# K84.net
KiCad netlist of a schematic drawn in EAGLE
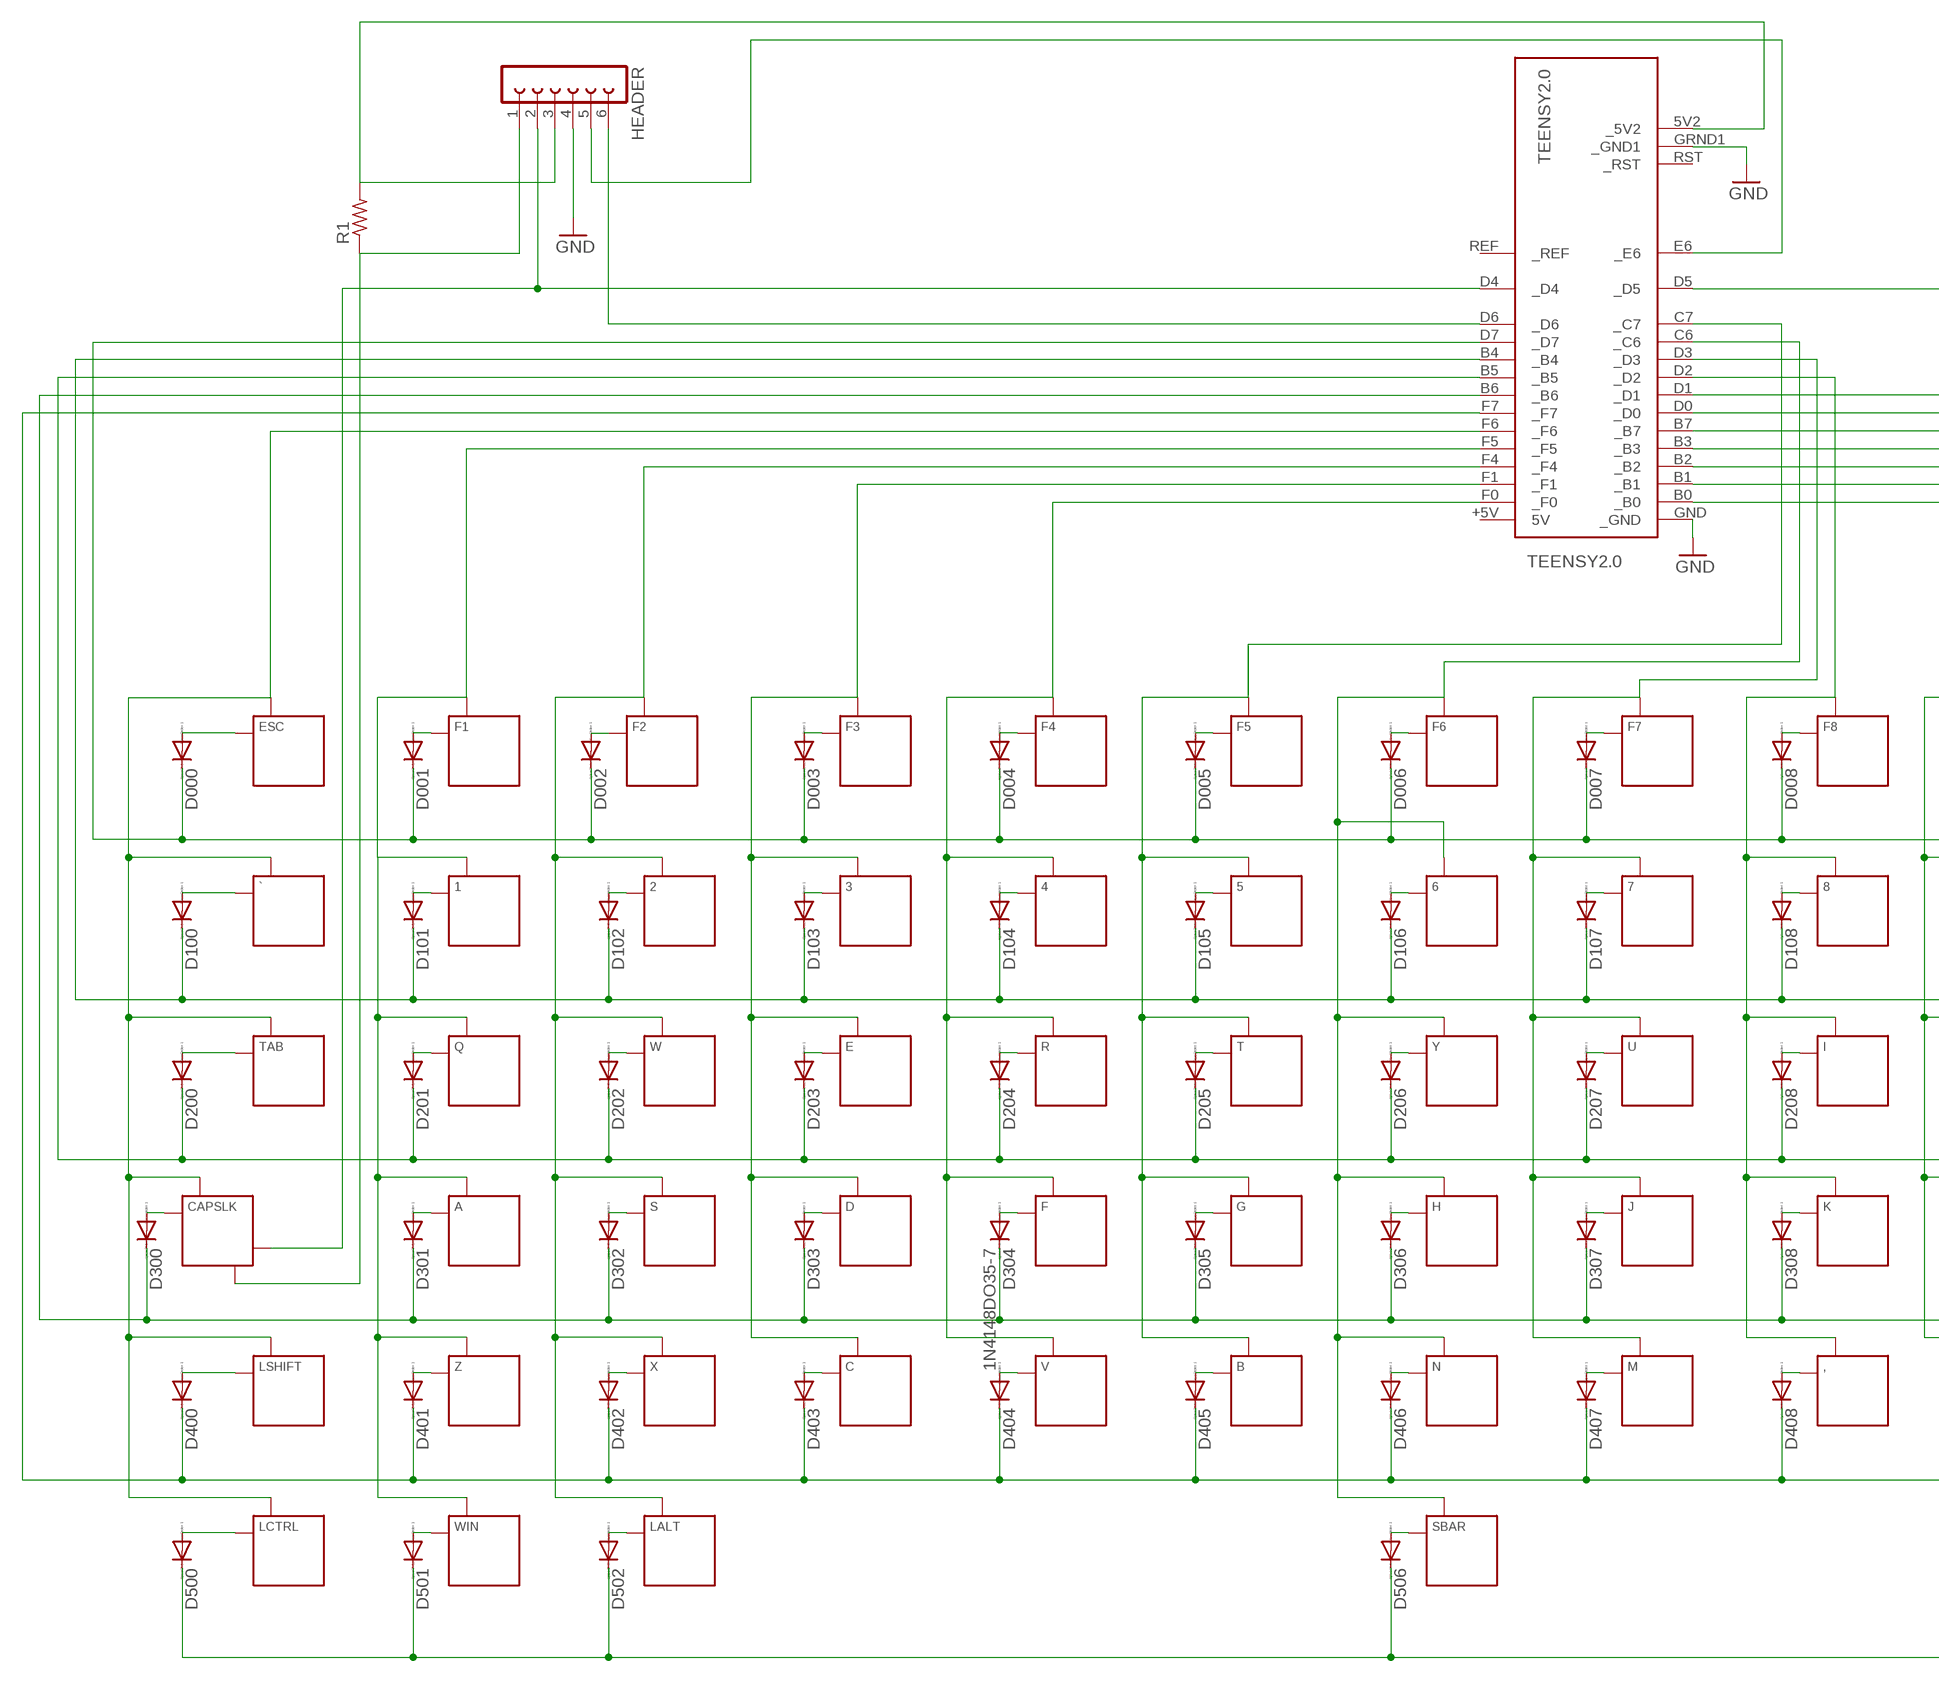
[diagram p0: schematic, sheet 1, part 1 of 2]
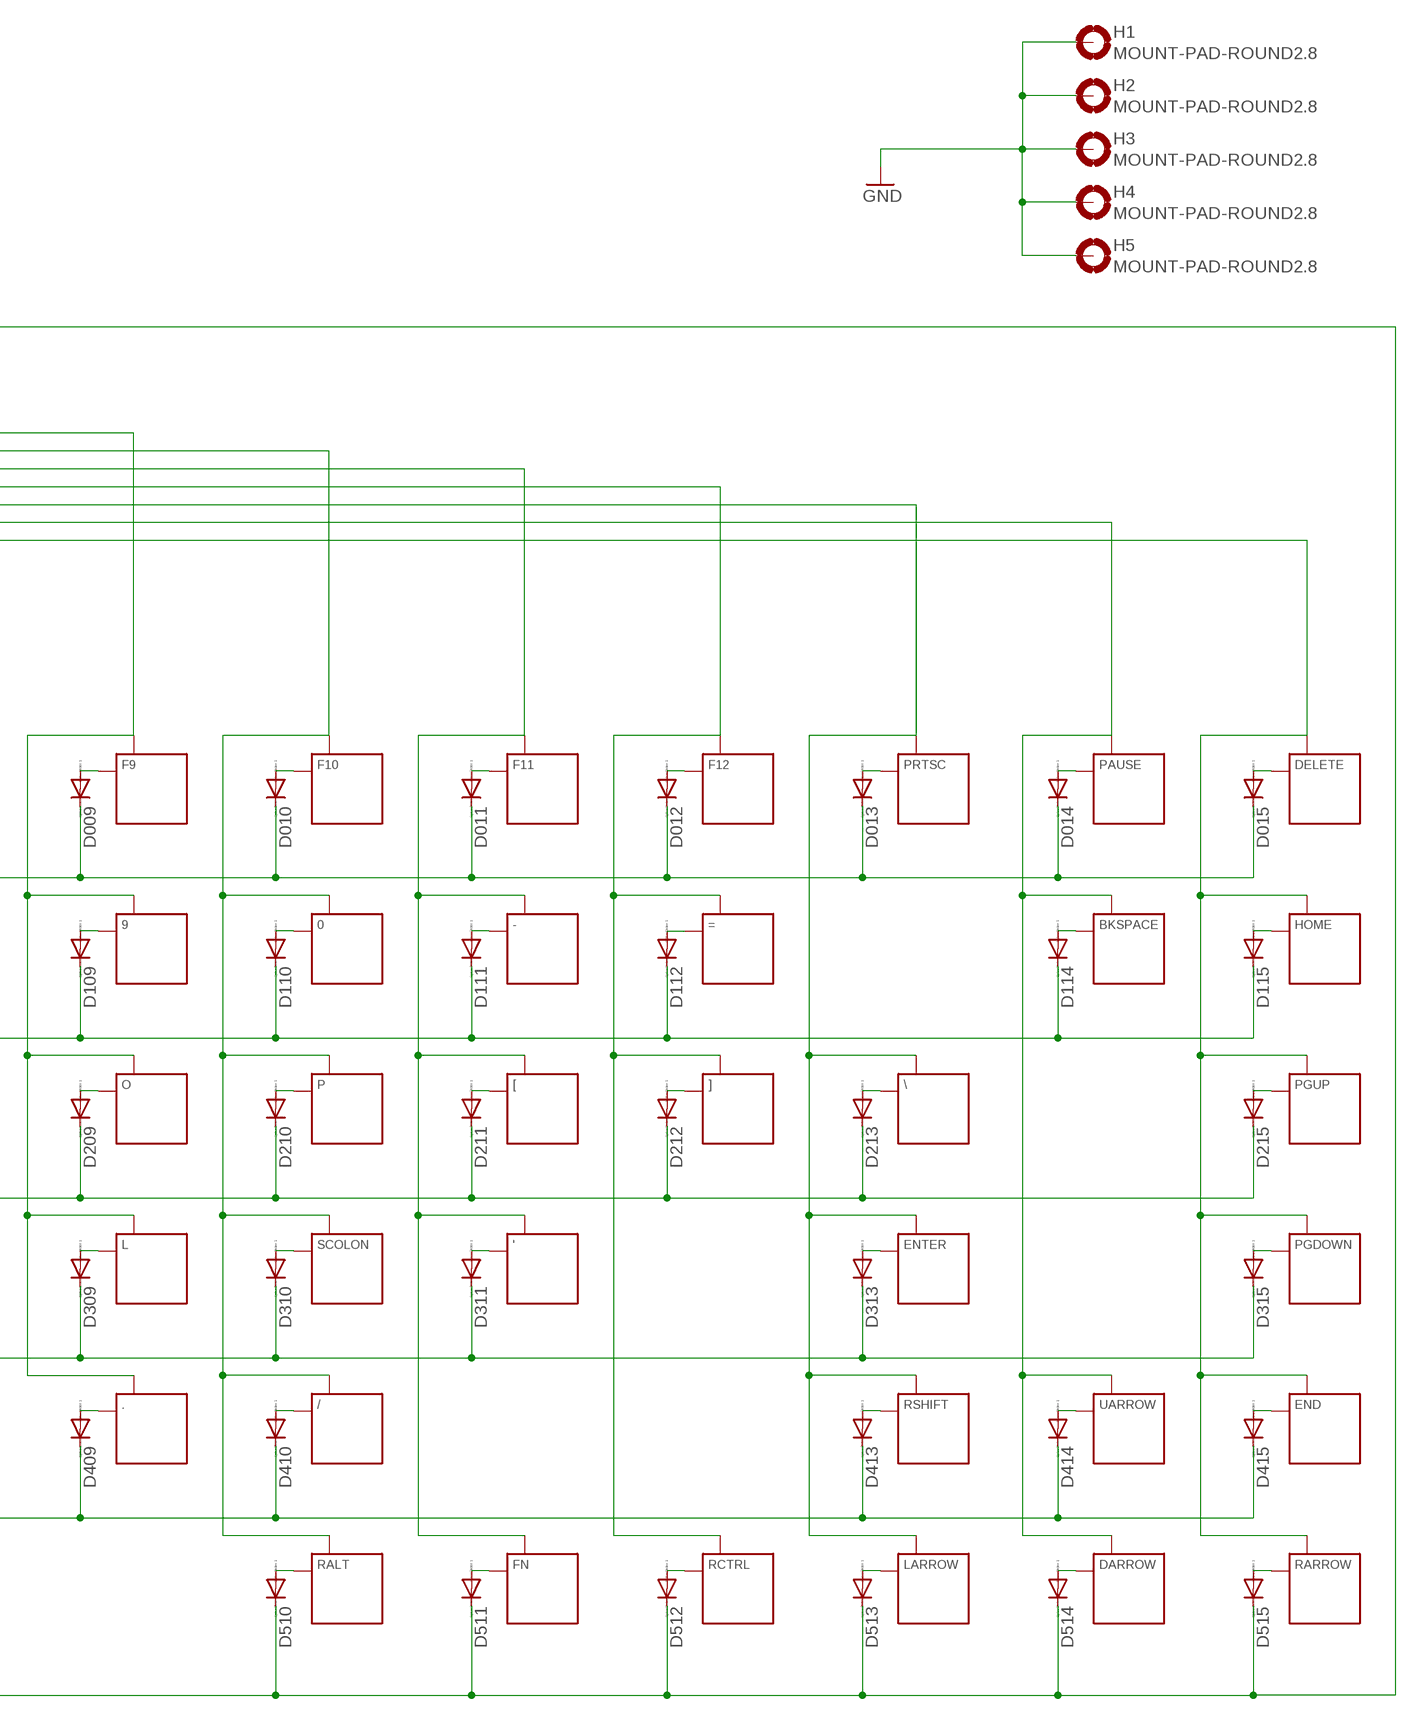
[diagram p1: schematic, sheet 1, part 2 of 2]

(export (version "E")
  (design (tool "Eeschema 10.0.6"))
  (components
    (comp (ref "'")
      (value "KEYSWITCH-PLAIN-MX-1U")
      (footprint "eagle-import:MX-1U")
      (libsource (lib "eagle-import") (part "KEYSWITCH-PLAIN-MX-1U"))
    )
    (comp (ref ",")
      (value "KEYSWITCH-PLAIN-MX-1U")
      (footprint "eagle-import:MX-1U")
      (libsource (lib "eagle-import") (part "KEYSWITCH-PLAIN-MX-1U"))
    )
    (comp (ref "-")
      (value "KEYSWITCH-PLAIN-MX-1U")
      (footprint "eagle-import:MX-1U")
      (libsource (lib "eagle-import") (part "KEYSWITCH-PLAIN-MX-1U"))
    )
    (comp (ref ".")
      (value "KEYSWITCH-PLAIN-MX-1U")
      (footprint "eagle-import:MX-1U")
      (libsource (lib "eagle-import") (part "KEYSWITCH-PLAIN-MX-1U"))
    )
    (comp (ref "/")
      (value "KEYSWITCH-PLAIN-MX-1U")
      (footprint "eagle-import:MX-1U")
      (libsource (lib "eagle-import") (part "KEYSWITCH-PLAIN-MX-1U"))
    )
    (comp (ref "0")
      (value "KEYSWITCH-PLAIN-MX-1U")
      (footprint "eagle-import:MX-1U")
      (libsource (lib "eagle-import") (part "KEYSWITCH-PLAIN-MX-1U"))
    )
    (comp (ref "1")
      (value "KEYSWITCH-PLAIN-MX-1U")
      (footprint "eagle-import:MX-1U")
      (libsource (lib "eagle-import") (part "KEYSWITCH-PLAIN-MX-1U"))
    )
    (comp (ref "2")
      (value "KEYSWITCH-PLAIN-MX-1U")
      (footprint "eagle-import:MX-1U")
      (libsource (lib "eagle-import") (part "KEYSWITCH-PLAIN-MX-1U"))
    )
    (comp (ref "3")
      (value "KEYSWITCH-PLAIN-MX-1U")
      (footprint "eagle-import:MX-1U")
      (libsource (lib "eagle-import") (part "KEYSWITCH-PLAIN-MX-1U"))
    )
    (comp (ref "4")
      (value "KEYSWITCH-PLAIN-MX-1U")
      (footprint "eagle-import:MX-1U")
      (libsource (lib "eagle-import") (part "KEYSWITCH-PLAIN-MX-1U"))
    )
    (comp (ref "5")
      (value "KEYSWITCH-PLAIN-MX-1U")
      (footprint "eagle-import:MX-1U")
      (libsource (lib "eagle-import") (part "KEYSWITCH-PLAIN-MX-1U"))
    )
    (comp (ref "6")
      (value "KEYSWITCH-PLAIN-MX-1U")
      (footprint "eagle-import:MX-1U")
      (libsource (lib "eagle-import") (part "KEYSWITCH-PLAIN-MX-1U"))
    )
    (comp (ref "7")
      (value "KEYSWITCH-PLAIN-MX-1U")
      (footprint "eagle-import:MX-1U")
      (libsource (lib "eagle-import") (part "KEYSWITCH-PLAIN-MX-1U"))
    )
    (comp (ref "8")
      (value "KEYSWITCH-PLAIN-MX-1U")
      (footprint "eagle-import:MX-1U")
      (libsource (lib "eagle-import") (part "KEYSWITCH-PLAIN-MX-1U"))
    )
    (comp (ref "9")
      (value "KEYSWITCH-PLAIN-MX-1U")
      (footprint "eagle-import:MX-1U")
      (libsource (lib "eagle-import") (part "KEYSWITCH-PLAIN-MX-1U"))
    )
    (comp (ref "=")
      (value "KEYSWITCH-PLAIN-MX-1U")
      (footprint "eagle-import:MX-1U")
      (libsource (lib "eagle-import") (part "KEYSWITCH-PLAIN-MX-1U"))
    )
    (comp (ref "A")
      (value "KEYSWITCH-PLAIN-MX-1U")
      (footprint "eagle-import:MX-1U")
      (libsource (lib "eagle-import") (part "KEYSWITCH-PLAIN-MX-1U"))
    )
    (comp (ref "B")
      (value "KEYSWITCH-PLAIN-MX-1U")
      (footprint "eagle-import:MX-1U")
      (libsource (lib "eagle-import") (part "KEYSWITCH-PLAIN-MX-1U"))
    )
    (comp (ref "BKSPACE")
      (value "KEYSWITCH-PLAIN-MX-2U")
      (footprint "eagle-import:MX-2U")
      (libsource (lib "eagle-import") (part "KEYSWITCH-PLAIN-MX-2U"))
    )
    (comp (ref "C")
      (value "KEYSWITCH-PLAIN-MX-1U")
      (footprint "eagle-import:MX-1U")
      (libsource (lib "eagle-import") (part "KEYSWITCH-PLAIN-MX-1U"))
    )
    (comp (ref "CAPSLK")
      (value "KEYSWITCH-LED-MX-1U-LED")
      (footprint "eagle-import:MX-1U-LED")
      (libsource (lib "eagle-import") (part "KEYSWITCH-LED-MX-1U-LED"))
    )
    (comp (ref "D")
      (value "KEYSWITCH-PLAIN-MX-1U")
      (footprint "eagle-import:MX-1U")
      (libsource (lib "eagle-import") (part "KEYSWITCH-PLAIN-MX-1U"))
    )
    (comp (ref "D000")
      (value "1N4148DO35-7")
      (footprint "eagle-import:DO35-7")
      (libsource (lib "eagle-import") (part "1N4148DO35-7"))
    )
    (comp (ref "D001")
      (value "1N4148DO35-7")
      (footprint "eagle-import:DO35-7")
      (libsource (lib "eagle-import") (part "1N4148DO35-7"))
    )
    (comp (ref "D002")
      (value "1N4148DO35-7")
      (footprint "eagle-import:DO35-7")
      (libsource (lib "eagle-import") (part "1N4148DO35-7"))
    )
    (comp (ref "D003")
      (value "1N4148DO35-7")
      (footprint "eagle-import:DO35-7")
      (libsource (lib "eagle-import") (part "1N4148DO35-7"))
    )
    (comp (ref "D004")
      (value "1N4148DO35-7")
      (footprint "eagle-import:DO35-7")
      (libsource (lib "eagle-import") (part "1N4148DO35-7"))
    )
    (comp (ref "D005")
      (value "1N4148DO35-7")
      (footprint "eagle-import:DO35-7")
      (libsource (lib "eagle-import") (part "1N4148DO35-7"))
    )
    (comp (ref "D006")
      (value "1N4148DO35-7")
      (footprint "eagle-import:DO35-7")
      (libsource (lib "eagle-import") (part "1N4148DO35-7"))
    )
    (comp (ref "D007")
      (value "1N4148DO35-7")
      (footprint "eagle-import:DO35-7")
      (libsource (lib "eagle-import") (part "1N4148DO35-7"))
    )
    (comp (ref "D008")
      (value "1N4148DO35-7")
      (footprint "eagle-import:DO35-7")
      (libsource (lib "eagle-import") (part "1N4148DO35-7"))
    )
    (comp (ref "D009")
      (value "1N4148DO35-7")
      (footprint "eagle-import:DO35-7")
      (libsource (lib "eagle-import") (part "1N4148DO35-7"))
    )
    (comp (ref "D010")
      (value "1N4148DO35-7")
      (footprint "eagle-import:DO35-7")
      (libsource (lib "eagle-import") (part "1N4148DO35-7"))
    )
    (comp (ref "D011")
      (value "1N4148DO35-7")
      (footprint "eagle-import:DO35-7")
      (libsource (lib "eagle-import") (part "1N4148DO35-7"))
    )
    (comp (ref "D012")
      (value "1N4148DO35-7")
      (footprint "eagle-import:DO35-7")
      (libsource (lib "eagle-import") (part "1N4148DO35-7"))
    )
    (comp (ref "D013")
      (value "1N4148DO35-7")
      (footprint "eagle-import:DO35-7")
      (libsource (lib "eagle-import") (part "1N4148DO35-7"))
    )
    (comp (ref "D014")
      (value "1N4148DO35-7")
      (footprint "eagle-import:DO35-7")
      (libsource (lib "eagle-import") (part "1N4148DO35-7"))
    )
    (comp (ref "D015")
      (value "1N4148DO35-7")
      (footprint "eagle-import:DO35-7")
      (libsource (lib "eagle-import") (part "1N4148DO35-7"))
    )
    (comp (ref "D100")
      (value "1N4148DO35-7")
      (footprint "eagle-import:DO35-7")
      (libsource (lib "eagle-import") (part "1N4148DO35-7"))
    )
    (comp (ref "D101")
      (value "1N4148DO35-7")
      (footprint "eagle-import:DO35-7")
      (libsource (lib "eagle-import") (part "1N4148DO35-7"))
    )
    (comp (ref "D102")
      (value "1N4148DO35-7")
      (footprint "eagle-import:DO35-7")
      (libsource (lib "eagle-import") (part "1N4148DO35-7"))
    )
    (comp (ref "D103")
      (value "1N4148DO35-7")
      (footprint "eagle-import:DO35-7")
      (libsource (lib "eagle-import") (part "1N4148DO35-7"))
    )
    (comp (ref "D104")
      (value "1N4148DO35-7")
      (footprint "eagle-import:DO35-7")
      (libsource (lib "eagle-import") (part "1N4148DO35-7"))
    )
    (comp (ref "D105")
      (value "1N4148DO35-7")
      (footprint "eagle-import:DO35-7")
      (libsource (lib "eagle-import") (part "1N4148DO35-7"))
    )
    (comp (ref "D106")
      (value "1N4148DO35-7")
      (footprint "eagle-import:DO35-7")
      (libsource (lib "eagle-import") (part "1N4148DO35-7"))
    )
    (comp (ref "D107")
      (value "1N4148DO35-7")
      (footprint "eagle-import:DO35-7")
      (libsource (lib "eagle-import") (part "1N4148DO35-7"))
    )
    (comp (ref "D108")
      (value "1N4148DO35-7")
      (footprint "eagle-import:DO35-7")
      (libsource (lib "eagle-import") (part "1N4148DO35-7"))
    )
    (comp (ref "D109")
      (value "1N4148DO35-7")
      (footprint "eagle-import:DO35-7")
      (libsource (lib "eagle-import") (part "1N4148DO35-7"))
    )
    (comp (ref "D110")
      (value "1N4148DO35-7")
      (footprint "eagle-import:DO35-7")
      (libsource (lib "eagle-import") (part "1N4148DO35-7"))
    )
    (comp (ref "D111")
      (value "1N4148DO35-7")
      (footprint "eagle-import:DO35-7")
      (libsource (lib "eagle-import") (part "1N4148DO35-7"))
    )
    (comp (ref "D112")
      (value "1N4148DO35-7")
      (footprint "eagle-import:DO35-7")
      (libsource (lib "eagle-import") (part "1N4148DO35-7"))
    )
    (comp (ref "D114")
      (value "1N4148DO35-7")
      (footprint "eagle-import:DO35-7")
      (libsource (lib "eagle-import") (part "1N4148DO35-7"))
    )
    (comp (ref "D115")
      (value "1N4148DO35-7")
      (footprint "eagle-import:DO35-7")
      (libsource (lib "eagle-import") (part "1N4148DO35-7"))
    )
    (comp (ref "D200")
      (value "1N4148DO35-7")
      (footprint "eagle-import:DO35-7")
      (libsource (lib "eagle-import") (part "1N4148DO35-7"))
    )
    (comp (ref "D201")
      (value "1N4148DO35-7")
      (footprint "eagle-import:DO35-7")
      (libsource (lib "eagle-import") (part "1N4148DO35-7"))
    )
    (comp (ref "D202")
      (value "1N4148DO35-7")
      (footprint "eagle-import:DO35-7")
      (libsource (lib "eagle-import") (part "1N4148DO35-7"))
    )
    (comp (ref "D203")
      (value "1N4148DO35-7")
      (footprint "eagle-import:DO35-7")
      (libsource (lib "eagle-import") (part "1N4148DO35-7"))
    )
    (comp (ref "D204")
      (value "1N4148DO35-7")
      (footprint "eagle-import:DO35-7")
      (libsource (lib "eagle-import") (part "1N4148DO35-7"))
    )
    (comp (ref "D205")
      (value "1N4148DO35-7")
      (footprint "eagle-import:DO35-7")
      (libsource (lib "eagle-import") (part "1N4148DO35-7"))
    )
    (comp (ref "D206")
      (value "1N4148DO35-7")
      (footprint "eagle-import:DO35-7")
      (libsource (lib "eagle-import") (part "1N4148DO35-7"))
    )
    (comp (ref "D207")
      (value "1N4148DO35-7")
      (footprint "eagle-import:DO35-7")
      (libsource (lib "eagle-import") (part "1N4148DO35-7"))
    )
    (comp (ref "D208")
      (value "1N4148DO35-7")
      (footprint "eagle-import:DO35-7")
      (libsource (lib "eagle-import") (part "1N4148DO35-7"))
    )
    (comp (ref "D209")
      (value "1N4148DO35-7")
      (footprint "eagle-import:DO35-7")
      (libsource (lib "eagle-import") (part "1N4148DO35-7"))
    )
    (comp (ref "D210")
      (value "1N4148DO35-7")
      (footprint "eagle-import:DO35-7")
      (libsource (lib "eagle-import") (part "1N4148DO35-7"))
    )
    (comp (ref "D211")
      (value "1N4148DO35-7")
      (footprint "eagle-import:DO35-7")
      (libsource (lib "eagle-import") (part "1N4148DO35-7"))
    )
    (comp (ref "D212")
      (value "1N4148DO35-7")
      (footprint "eagle-import:DO35-7")
      (libsource (lib "eagle-import") (part "1N4148DO35-7"))
    )
    (comp (ref "D213")
      (value "1N4148DO35-7")
      (footprint "eagle-import:DO35-7")
      (libsource (lib "eagle-import") (part "1N4148DO35-7"))
    )
    (comp (ref "D215")
      (value "1N4148DO35-7")
      (footprint "eagle-import:DO35-7")
      (libsource (lib "eagle-import") (part "1N4148DO35-7"))
    )
    (comp (ref "D300")
      (value "1N4148DO35-7")
      (footprint "eagle-import:DO35-7")
      (libsource (lib "eagle-import") (part "1N4148DO35-7"))
    )
    (comp (ref "D301")
      (value "1N4148DO35-7")
      (footprint "eagle-import:DO35-7")
      (libsource (lib "eagle-import") (part "1N4148DO35-7"))
    )
    (comp (ref "D302")
      (value "1N4148DO35-7")
      (footprint "eagle-import:DO35-7")
      (libsource (lib "eagle-import") (part "1N4148DO35-7"))
    )
    (comp (ref "D303")
      (value "1N4148DO35-7")
      (footprint "eagle-import:DO35-7")
      (libsource (lib "eagle-import") (part "1N4148DO35-7"))
    )
    (comp (ref "D304")
      (value "1N4148DO35-7")
      (footprint "eagle-import:DO35-7")
      (libsource (lib "eagle-import") (part "1N4148DO35-7"))
    )
    (comp (ref "D305")
      (value "1N4148DO35-7")
      (footprint "eagle-import:DO35-7")
      (libsource (lib "eagle-import") (part "1N4148DO35-7"))
    )
    (comp (ref "D306")
      (value "1N4148DO35-7")
      (footprint "eagle-import:DO35-7")
      (libsource (lib "eagle-import") (part "1N4148DO35-7"))
    )
    (comp (ref "D307")
      (value "1N4148DO35-7")
      (footprint "eagle-import:DO35-7")
      (libsource (lib "eagle-import") (part "1N4148DO35-7"))
    )
    (comp (ref "D308")
      (value "1N4148DO35-7")
      (footprint "eagle-import:DO35-7")
      (libsource (lib "eagle-import") (part "1N4148DO35-7"))
    )
    (comp (ref "D309")
      (value "1N4148DO35-7")
      (footprint "eagle-import:DO35-7")
      (libsource (lib "eagle-import") (part "1N4148DO35-7"))
    )
    (comp (ref "D310")
      (value "1N4148DO35-7")
      (footprint "eagle-import:DO35-7")
      (libsource (lib "eagle-import") (part "1N4148DO35-7"))
    )
    (comp (ref "D311")
      (value "1N4148DO35-7")
      (footprint "eagle-import:DO35-7")
      (libsource (lib "eagle-import") (part "1N4148DO35-7"))
    )
    (comp (ref "D313")
      (value "1N4148DO35-7")
      (footprint "eagle-import:DO35-7")
      (libsource (lib "eagle-import") (part "1N4148DO35-7"))
    )
    (comp (ref "D315")
      (value "1N4148DO35-7")
      (footprint "eagle-import:DO35-7")
      (libsource (lib "eagle-import") (part "1N4148DO35-7"))
    )
    (comp (ref "D400")
      (value "1N4148DO35-7")
      (footprint "eagle-import:DO35-7")
      (libsource (lib "eagle-import") (part "1N4148DO35-7"))
    )
    (comp (ref "D401")
      (value "1N4148DO35-7")
      (footprint "eagle-import:DO35-7")
      (libsource (lib "eagle-import") (part "1N4148DO35-7"))
    )
    (comp (ref "D402")
      (value "1N4148DO35-7")
      (footprint "eagle-import:DO35-7")
      (libsource (lib "eagle-import") (part "1N4148DO35-7"))
    )
    (comp (ref "D403")
      (value "1N4148DO35-7")
      (footprint "eagle-import:DO35-7")
      (libsource (lib "eagle-import") (part "1N4148DO35-7"))
    )
    (comp (ref "D404")
      (value "1N4148DO35-7")
      (footprint "eagle-import:DO35-7")
      (libsource (lib "eagle-import") (part "1N4148DO35-7"))
    )
    (comp (ref "D405")
      (value "1N4148DO35-7")
      (footprint "eagle-import:DO35-7")
      (libsource (lib "eagle-import") (part "1N4148DO35-7"))
    )
    (comp (ref "D406")
      (value "1N4148DO35-7")
      (footprint "eagle-import:DO35-7")
      (libsource (lib "eagle-import") (part "1N4148DO35-7"))
    )
    (comp (ref "D407")
      (value "1N4148DO35-7")
      (footprint "eagle-import:DO35-7")
      (libsource (lib "eagle-import") (part "1N4148DO35-7"))
    )
    (comp (ref "D408")
      (value "1N4148DO35-7")
      (footprint "eagle-import:DO35-7")
      (libsource (lib "eagle-import") (part "1N4148DO35-7"))
    )
    (comp (ref "D409")
      (value "1N4148DO35-7")
      (footprint "eagle-import:DO35-7")
      (libsource (lib "eagle-import") (part "1N4148DO35-7"))
    )
    (comp (ref "D410")
      (value "1N4148DO35-7")
      (footprint "eagle-import:DO35-7")
      (libsource (lib "eagle-import") (part "1N4148DO35-7"))
    )
    (comp (ref "D413")
      (value "1N4148DO35-7")
      (footprint "eagle-import:DO35-7")
      (libsource (lib "eagle-import") (part "1N4148DO35-7"))
    )
    (comp (ref "D414")
      (value "1N4148DO35-7")
      (footprint "eagle-import:DO35-7")
      (libsource (lib "eagle-import") (part "1N4148DO35-7"))
    )
    (comp (ref "D415")
      (value "1N4148DO35-7")
      (footprint "eagle-import:DO35-7")
      (libsource (lib "eagle-import") (part "1N4148DO35-7"))
    )
    (comp (ref "D500")
      (value "1N4148DO35-7")
      (footprint "eagle-import:DO35-7")
      (libsource (lib "eagle-import") (part "1N4148DO35-7"))
    )
    (comp (ref "D501")
      (value "1N4148DO35-7")
      (footprint "eagle-import:DO35-7")
      (libsource (lib "eagle-import") (part "1N4148DO35-7"))
    )
    (comp (ref "D502")
      (value "1N4148DO35-7")
      (footprint "eagle-import:DO35-7")
      (libsource (lib "eagle-import") (part "1N4148DO35-7"))
    )
    (comp (ref "D506")
      (value "1N4148DO35-7")
      (footprint "eagle-import:DO35-7")
      (libsource (lib "eagle-import") (part "1N4148DO35-7"))
    )
    (comp (ref "D510")
      (value "1N4148DO35-7")
      (footprint "eagle-import:DO35-7")
      (libsource (lib "eagle-import") (part "1N4148DO35-7"))
    )
    (comp (ref "D511")
      (value "1N4148DO35-7")
      (footprint "eagle-import:DO35-7")
      (libsource (lib "eagle-import") (part "1N4148DO35-7"))
    )
    (comp (ref "D512")
      (value "1N4148DO35-7")
      (footprint "eagle-import:DO35-7")
      (libsource (lib "eagle-import") (part "1N4148DO35-7"))
    )
    (comp (ref "D513")
      (value "1N4148DO35-7")
      (footprint "eagle-import:DO35-7")
      (libsource (lib "eagle-import") (part "1N4148DO35-7"))
    )
    (comp (ref "D514")
      (value "1N4148DO35-7")
      (footprint "eagle-import:DO35-7")
      (libsource (lib "eagle-import") (part "1N4148DO35-7"))
    )
    (comp (ref "D515")
      (value "1N4148DO35-7")
      (footprint "eagle-import:DO35-7")
      (libsource (lib "eagle-import") (part "1N4148DO35-7"))
    )
    (comp (ref "DARROW")
      (value "KEYSWITCH-PLAIN-MX-1U")
      (footprint "eagle-import:MX-1U")
      (libsource (lib "eagle-import") (part "KEYSWITCH-PLAIN-MX-1U"))
    )
    (comp (ref "DELETE")
      (value "KEYSWITCH-PLAIN-MX-1U")
      (footprint "eagle-import:MX-1U")
      (libsource (lib "eagle-import") (part "KEYSWITCH-PLAIN-MX-1U"))
    )
    (comp (ref "E")
      (value "KEYSWITCH-PLAIN-MX-1U")
      (footprint "eagle-import:MX-1U")
      (libsource (lib "eagle-import") (part "KEYSWITCH-PLAIN-MX-1U"))
    )
    (comp (ref "END")
      (value "KEYSWITCH-PLAIN-MX-1U")
      (footprint "eagle-import:MX-1U")
      (libsource (lib "eagle-import") (part "KEYSWITCH-PLAIN-MX-1U"))
    )
    (comp (ref "ENTER")
      (value "KEYSWITCH-PLAIN-MX-2U")
      (footprint "eagle-import:MX-2U")
      (libsource (lib "eagle-import") (part "KEYSWITCH-PLAIN-MX-2U"))
    )
    (comp (ref "ESC")
      (value "S001")
      (footprint "eagle-import:MX-1U")
      (libsource (lib "eagle-import") (part "KEYSWITCH-PLAIN-MX-1U"))
    )
    (comp (ref "F")
      (value "KEYSWITCH-PLAIN-MX-1U")
      (footprint "eagle-import:MX-1U")
      (libsource (lib "eagle-import") (part "KEYSWITCH-PLAIN-MX-1U"))
    )
    (comp (ref "F1")
      (value "KEYSWITCH-PLAIN-MX-1U")
      (footprint "eagle-import:MX-1U")
      (libsource (lib "eagle-import") (part "KEYSWITCH-PLAIN-MX-1U"))
    )
    (comp (ref "F2")
      (value "KEYSWITCH-PLAIN-MX-1U")
      (footprint "eagle-import:MX-1U")
      (libsource (lib "eagle-import") (part "KEYSWITCH-PLAIN-MX-1U"))
    )
    (comp (ref "F3")
      (value "KEYSWITCH-PLAIN-MX-1U")
      (footprint "eagle-import:MX-1U")
      (libsource (lib "eagle-import") (part "KEYSWITCH-PLAIN-MX-1U"))
    )
    (comp (ref "F4")
      (value "KEYSWITCH-PLAIN-MX-1U")
      (footprint "eagle-import:MX-1U")
      (libsource (lib "eagle-import") (part "KEYSWITCH-PLAIN-MX-1U"))
    )
    (comp (ref "F5")
      (value "KEYSWITCH-PLAIN-MX-1U")
      (footprint "eagle-import:MX-1U")
      (libsource (lib "eagle-import") (part "KEYSWITCH-PLAIN-MX-1U"))
    )
    (comp (ref "F6")
      (value "KEYSWITCH-PLAIN-MX-1U")
      (footprint "eagle-import:MX-1U")
      (libsource (lib "eagle-import") (part "KEYSWITCH-PLAIN-MX-1U"))
    )
    (comp (ref "F7")
      (value "KEYSWITCH-PLAIN-MX-1U")
      (footprint "eagle-import:MX-1U")
      (libsource (lib "eagle-import") (part "KEYSWITCH-PLAIN-MX-1U"))
    )
    (comp (ref "F8")
      (value "KEYSWITCH-PLAIN-MX-1U")
      (footprint "eagle-import:MX-1U")
      (libsource (lib "eagle-import") (part "KEYSWITCH-PLAIN-MX-1U"))
    )
    (comp (ref "F9")
      (value "KEYSWITCH-PLAIN-MX-1U")
      (footprint "eagle-import:MX-1U")
      (libsource (lib "eagle-import") (part "KEYSWITCH-PLAIN-MX-1U"))
    )
    (comp (ref "F10")
      (value "KEYSWITCH-PLAIN-MX-1U")
      (footprint "eagle-import:MX-1U")
      (libsource (lib "eagle-import") (part "KEYSWITCH-PLAIN-MX-1U"))
    )
    (comp (ref "F11")
      (value "KEYSWITCH-PLAIN-MX-1U")
      (footprint "eagle-import:MX-1U")
      (libsource (lib "eagle-import") (part "KEYSWITCH-PLAIN-MX-1U"))
    )
    (comp (ref "F12")
      (value "KEYSWITCH-PLAIN-MX-1U")
      (footprint "eagle-import:MX-1U")
      (libsource (lib "eagle-import") (part "KEYSWITCH-PLAIN-MX-1U"))
    )
    (comp (ref "FN")
      (value "KEYSWITCH-PLAIN-MX-1U")
      (footprint "eagle-import:MX-1U")
      (libsource (lib "eagle-import") (part "KEYSWITCH-PLAIN-MX-1U"))
    )
    (comp (ref "G")
      (value "KEYSWITCH-PLAIN-MX-1U")
      (footprint "eagle-import:MX-1U")
      (libsource (lib "eagle-import") (part "KEYSWITCH-PLAIN-MX-1U"))
    )
    (comp (ref "H")
      (value "KEYSWITCH-PLAIN-MX-1U")
      (footprint "eagle-import:MX-1U")
      (libsource (lib "eagle-import") (part "KEYSWITCH-PLAIN-MX-1U"))
    )
    (comp (ref "H1")
      (value "MOUNT-PAD-ROUND2.8")
      (footprint "eagle-import:2,8-PAD")
      (libsource (lib "eagle-import") (part "MOUNT-PAD-ROUND2.8"))
    )
    (comp (ref "H2")
      (value "MOUNT-PAD-ROUND2.8")
      (footprint "eagle-import:2,8-PAD")
      (libsource (lib "eagle-import") (part "MOUNT-PAD-ROUND2.8"))
    )
    (comp (ref "H3")
      (value "MOUNT-PAD-ROUND2.8")
      (footprint "eagle-import:2,8-PAD")
      (libsource (lib "eagle-import") (part "MOUNT-PAD-ROUND2.8"))
    )
    (comp (ref "H4")
      (value "MOUNT-PAD-ROUND2.8")
      (footprint "eagle-import:2,8-PAD")
      (libsource (lib "eagle-import") (part "MOUNT-PAD-ROUND2.8"))
    )
    (comp (ref "H5")
      (value "MOUNT-PAD-ROUND2.8")
      (footprint "eagle-import:2,8-PAD")
      (libsource (lib "eagle-import") (part "MOUNT-PAD-ROUND2.8"))
    )
    (comp (ref "HEADER")
      (value "FE06-1")
      (footprint "eagle-import:FE06")
      (libsource (lib "eagle-import") (part "FE06-1"))
    )
    (comp (ref "HOME")
      (value "KEYSWITCH-PLAIN-MX-1U")
      (footprint "eagle-import:MX-1U")
      (libsource (lib "eagle-import") (part "KEYSWITCH-PLAIN-MX-1U"))
    )
    (comp (ref "I")
      (value "KEYSWITCH-PLAIN-MX-1U")
      (footprint "eagle-import:MX-1U")
      (libsource (lib "eagle-import") (part "KEYSWITCH-PLAIN-MX-1U"))
    )
    (comp (ref "J")
      (value "KEYSWITCH-PLAIN-MX-1U")
      (footprint "eagle-import:MX-1U")
      (libsource (lib "eagle-import") (part "KEYSWITCH-PLAIN-MX-1U"))
    )
    (comp (ref "K")
      (value "KEYSWITCH-PLAIN-MX-1U")
      (footprint "eagle-import:MX-1U")
      (libsource (lib "eagle-import") (part "KEYSWITCH-PLAIN-MX-1U"))
    )
    (comp (ref "L")
      (value "KEYSWITCH-PLAIN-MX-1U")
      (footprint "eagle-import:MX-1U")
      (libsource (lib "eagle-import") (part "KEYSWITCH-PLAIN-MX-1U"))
    )
    (comp (ref "LALT")
      (value "KEYSWITCH-PLAIN-MX-1U")
      (footprint "eagle-import:MX-1U")
      (libsource (lib "eagle-import") (part "KEYSWITCH-PLAIN-MX-1U"))
    )
    (comp (ref "LARROW")
      (value "KEYSWITCH-PLAIN-MX-1U")
      (footprint "eagle-import:MX-1U")
      (libsource (lib "eagle-import") (part "KEYSWITCH-PLAIN-MX-1U"))
    )
    (comp (ref "LCTRL")
      (value "KEYSWITCH-PLAIN-MX-1U")
      (footprint "eagle-import:MX-1U")
      (libsource (lib "eagle-import") (part "KEYSWITCH-PLAIN-MX-1U"))
    )
    (comp (ref "LSHIFT")
      (value "KEYSWITCH-PLAIN-MX-2U")
      (footprint "eagle-import:MX-2U")
      (libsource (lib "eagle-import") (part "KEYSWITCH-PLAIN-MX-2U"))
    )
    (comp (ref "M")
      (value "KEYSWITCH-PLAIN-MX-1U")
      (footprint "eagle-import:MX-1U")
      (libsource (lib "eagle-import") (part "KEYSWITCH-PLAIN-MX-1U"))
    )
    (comp (ref "N")
      (value "KEYSWITCH-PLAIN-MX-1U")
      (footprint "eagle-import:MX-1U")
      (libsource (lib "eagle-import") (part "KEYSWITCH-PLAIN-MX-1U"))
    )
    (comp (ref "O")
      (value "KEYSWITCH-PLAIN-MX-1U")
      (footprint "eagle-import:MX-1U")
      (libsource (lib "eagle-import") (part "KEYSWITCH-PLAIN-MX-1U"))
    )
    (comp (ref "P")
      (value "KEYSWITCH-PLAIN-MX-1U")
      (footprint "eagle-import:MX-1U")
      (libsource (lib "eagle-import") (part "KEYSWITCH-PLAIN-MX-1U"))
    )
    (comp (ref "PAUSE")
      (value "KEYSWITCH-PLAIN-MX-1U")
      (footprint "eagle-import:MX-1U")
      (libsource (lib "eagle-import") (part "KEYSWITCH-PLAIN-MX-1U"))
    )
    (comp (ref "PGDOWN")
      (value "KEYSWITCH-PLAIN-MX-1U")
      (footprint "eagle-import:MX-1U")
      (libsource (lib "eagle-import") (part "KEYSWITCH-PLAIN-MX-1U"))
    )
    (comp (ref "PGUP")
      (value "KEYSWITCH-PLAIN-MX-1U")
      (footprint "eagle-import:MX-1U")
      (libsource (lib "eagle-import") (part "KEYSWITCH-PLAIN-MX-1U"))
    )
    (comp (ref "PRTSC")
      (value "KEYSWITCH-PLAIN-MX-1U")
      (footprint "eagle-import:MX-1U")
      (libsource (lib "eagle-import") (part "KEYSWITCH-PLAIN-MX-1U"))
    )
    (comp (ref "Q")
      (value "KEYSWITCH-PLAIN-MX-1U")
      (footprint "eagle-import:MX-1U")
      (libsource (lib "eagle-import") (part "KEYSWITCH-PLAIN-MX-1U"))
    )
    (comp (ref "R")
      (value "KEYSWITCH-PLAIN-MX-1U")
      (footprint "eagle-import:MX-1U")
      (libsource (lib "eagle-import") (part "KEYSWITCH-PLAIN-MX-1U"))
    )
    (comp (ref "R1")
      (value "R-US_0204/7")
      (footprint "eagle-import:0204_7")
      (libsource (lib "eagle-import") (part "R-US_0204/7"))
    )
    (comp (ref "RALT")
      (value "KEYSWITCH-PLAIN-MX-1U")
      (footprint "eagle-import:MX-1U")
      (libsource (lib "eagle-import") (part "KEYSWITCH-PLAIN-MX-1U"))
    )
    (comp (ref "RARROW")
      (value "KEYSWITCH-PLAIN-MX-1U")
      (footprint "eagle-import:MX-1U")
      (libsource (lib "eagle-import") (part "KEYSWITCH-PLAIN-MX-1U"))
    )
    (comp (ref "RCTRL")
      (value "KEYSWITCH-PLAIN-MX-1U")
      (footprint "eagle-import:MX-1U")
      (libsource (lib "eagle-import") (part "KEYSWITCH-PLAIN-MX-1U"))
    )
    (comp (ref "RSHIFT")
      (value "KEYSWITCH-PLAIN-MX-1U")
      (footprint "eagle-import:MX-1U")
      (libsource (lib "eagle-import") (part "KEYSWITCH-PLAIN-MX-1U"))
    )
    (comp (ref "S")
      (value "KEYSWITCH-PLAIN-MX-1U")
      (footprint "eagle-import:MX-1U")
      (libsource (lib "eagle-import") (part "KEYSWITCH-PLAIN-MX-1U"))
    )
    (comp (ref "SBAR")
      (value "KEYSWITCH-PLAIN-MX-6.25U-FLIPPED")
      (footprint "eagle-import:MX-6.25U-FLIPPED")
      (libsource (lib "eagle-import") (part "KEYSWITCH-PLAIN-MX-6.25U-FLIPPED"))
    )
    (comp (ref "SCOLON")
      (value "KEYSWITCH-PLAIN-MX-1U")
      (footprint "eagle-import:MX-1U")
      (libsource (lib "eagle-import") (part "KEYSWITCH-PLAIN-MX-1U"))
    )
    (comp (ref "T")
      (value "KEYSWITCH-PLAIN-MX-1U")
      (footprint "eagle-import:MX-1U")
      (libsource (lib "eagle-import") (part "KEYSWITCH-PLAIN-MX-1U"))
    )
    (comp (ref "TAB")
      (value "KEYSWITCH-PLAIN-MX-1U")
      (footprint "eagle-import:MX-1U")
      (libsource (lib "eagle-import") (part "KEYSWITCH-PLAIN-MX-1U"))
    )
    (comp (ref "TEENSY2.0")
      (value "TEENSY2.0")
      (footprint "eagle-import:TEENSY2.0")
      (libsource (lib "eagle-import") (part "TEENSY2.0"))
    )
    (comp (ref "U")
      (value "KEYSWITCH-PLAIN-MX-1U")
      (footprint "eagle-import:MX-1U")
      (libsource (lib "eagle-import") (part "KEYSWITCH-PLAIN-MX-1U"))
    )
    (comp (ref "UARROW")
      (value "KEYSWITCH-PLAIN-MX-1U")
      (footprint "eagle-import:MX-1U")
      (libsource (lib "eagle-import") (part "KEYSWITCH-PLAIN-MX-1U"))
    )
    (comp (ref "V")
      (value "KEYSWITCH-PLAIN-MX-1U")
      (footprint "eagle-import:MX-1U")
      (libsource (lib "eagle-import") (part "KEYSWITCH-PLAIN-MX-1U"))
    )
    (comp (ref "W")
      (value "KEYSWITCH-PLAIN-MX-1U")
      (footprint "eagle-import:MX-1U")
      (libsource (lib "eagle-import") (part "KEYSWITCH-PLAIN-MX-1U"))
    )
    (comp (ref "WIN")
      (value "KEYSWITCH-PLAIN-MX-1U")
      (footprint "eagle-import:MX-1U")
      (libsource (lib "eagle-import") (part "KEYSWITCH-PLAIN-MX-1U"))
    )
    (comp (ref "X")
      (value "KEYSWITCH-PLAIN-MX-1U")
      (footprint "eagle-import:MX-1U")
      (libsource (lib "eagle-import") (part "KEYSWITCH-PLAIN-MX-1U"))
    )
    (comp (ref "Y")
      (value "KEYSWITCH-PLAIN-MX-1U")
      (footprint "eagle-import:MX-1U")
      (libsource (lib "eagle-import") (part "KEYSWITCH-PLAIN-MX-1U"))
    )
    (comp (ref "Z")
      (value "KEYSWITCH-PLAIN-MX-1U")
      (footprint "eagle-import:MX-1U")
      (libsource (lib "eagle-import") (part "KEYSWITCH-PLAIN-MX-1U"))
    )
    (comp (ref "[")
      (value "KEYSWITCH-PLAIN-MX-1U")
      (footprint "eagle-import:MX-1U")
      (libsource (lib "eagle-import") (part "KEYSWITCH-PLAIN-MX-1U"))
    )
    (comp (ref "\\\\")
      (value "KEYSWITCH-PLAIN-MX-1U")
      (footprint "eagle-import:MX-1U")
      (libsource (lib "eagle-import") (part "KEYSWITCH-PLAIN-MX-1U"))
    )
    (comp (ref "]")
      (value "KEYSWITCH-PLAIN-MX-1U")
      (footprint "eagle-import:MX-1U")
      (libsource (lib "eagle-import") (part "KEYSWITCH-PLAIN-MX-1U"))
    )
    (comp (ref "`")
      (value "KEYSWITCH-PLAIN-MX-1U")
      (footprint "eagle-import:MX-1U")
      (libsource (lib "eagle-import") (part "KEYSWITCH-PLAIN-MX-1U"))
    )
  )
  (nets
    (net (code "1") (name "GND") (class "Default")
      (node (ref "H1") (pin "B2,8") (pinfunction "MOUNT_B2,8") (pintype "passive"))
      (node (ref "H2") (pin "B2,8") (pinfunction "MOUNT_B2,8") (pintype "passive"))
      (node (ref "H3") (pin "B2,8") (pinfunction "MOUNT_B2,8") (pintype "passive"))
      (node (ref "H4") (pin "B2,8") (pinfunction "MOUNT_B2,8") (pintype "passive"))
      (node (ref "H5") (pin "B2,8") (pinfunction "MOUNT_B2,8") (pintype "passive"))
      (node (ref "HEADER") (pin "4") (pinfunction "4_4") (pintype "passive"))
      (node (ref "TEENSY2.0") (pin "GND") (pinfunction "_GND_GND") (pintype "bidirectional"))
      (node (ref "TEENSY2.0") (pin "GRND1") (pinfunction "_GND1_GRND1") (pintype "bidirectional"))
    )
    (net (code "2") (name "Net-('-P0)") (class "Default")
      (node (ref "'") (pin "MX1") (pinfunction "P0_MX1") (pintype "bidirectional"))
      (node (ref "D311") (pin "A") (pinfunction "A_A") (pintype "passive"))
    )
    (net (code "3") (name "Net-('-P1)") (class "Default")
      (node (ref "'") (pin "MX2") (pinfunction "P1_MX2") (pintype "bidirectional"))
      (node (ref "-") (pin "MX2") (pinfunction "P1_MX2") (pintype "bidirectional"))
      (node (ref "F11") (pin "MX2") (pinfunction "P1_MX2") (pintype "bidirectional"))
      (node (ref "FN") (pin "MX2") (pinfunction "P1_MX2") (pintype "bidirectional"))
      (node (ref "TEENSY2.0") (pin "B7") (pinfunction "_B7_B7") (pintype "bidirectional"))
      (node (ref "[") (pin "MX2") (pinfunction "P1_MX2") (pintype "bidirectional"))
    )
    (net (code "4") (name "Net-(,-P0)") (class "Default")
      (node (ref ",") (pin "MX1") (pinfunction "P0_MX1") (pintype "bidirectional"))
      (node (ref "D408") (pin "A") (pinfunction "A_A") (pintype "passive"))
    )
    (net (code "5") (name "Net-(,-P1)") (class "Default")
      (node (ref ",") (pin "MX2") (pinfunction "P1_MX2") (pintype "bidirectional"))
      (node (ref "8") (pin "MX2") (pinfunction "P1_MX2") (pintype "bidirectional"))
      (node (ref "F8") (pin "MX2") (pinfunction "P1_MX2") (pintype "bidirectional"))
      (node (ref "I") (pin "MX2") (pinfunction "P1_MX2") (pintype "bidirectional"))
      (node (ref "K") (pin "MX2") (pinfunction "P1_MX2") (pintype "bidirectional"))
      (node (ref "TEENSY2.0") (pin "D2") (pinfunction "_D2_D2") (pintype "bidirectional"))
    )
    (net (code "6") (name "Net-(--P0)") (class "Default")
      (node (ref "-") (pin "MX1") (pinfunction "P0_MX1") (pintype "bidirectional"))
      (node (ref "D111") (pin "A") (pinfunction "A_A") (pintype "passive"))
    )
    (net (code "7") (name "Net-(.-P0)") (class "Default")
      (node (ref ".") (pin "MX1") (pinfunction "P0_MX1") (pintype "bidirectional"))
      (node (ref "D409") (pin "A") (pinfunction "A_A") (pintype "passive"))
    )
    (net (code "8") (name "Net-(.-P1)") (class "Default")
      (node (ref ".") (pin "MX2") (pinfunction "P1_MX2") (pintype "bidirectional"))
      (node (ref "9") (pin "MX2") (pinfunction "P1_MX2") (pintype "bidirectional"))
      (node (ref "F9") (pin "MX2") (pinfunction "P1_MX2") (pintype "bidirectional"))
      (node (ref "L") (pin "MX2") (pinfunction "P1_MX2") (pintype "bidirectional"))
      (node (ref "O") (pin "MX2") (pinfunction "P1_MX2") (pintype "bidirectional"))
      (node (ref "TEENSY2.0") (pin "D1") (pinfunction "_D1_D1") (pintype "bidirectional"))
    )
    (net (code "9") (name "Net-(/-P0)") (class "Default")
      (node (ref "/") (pin "MX1") (pinfunction "P0_MX1") (pintype "bidirectional"))
      (node (ref "D410") (pin "A") (pinfunction "A_A") (pintype "passive"))
    )
    (net (code "10") (name "Net-(/-P1)") (class "Default")
      (node (ref "/") (pin "MX2") (pinfunction "P1_MX2") (pintype "bidirectional"))
      (node (ref "0") (pin "MX2") (pinfunction "P1_MX2") (pintype "bidirectional"))
      (node (ref "F10") (pin "MX2") (pinfunction "P1_MX2") (pintype "bidirectional"))
      (node (ref "P") (pin "MX2") (pinfunction "P1_MX2") (pintype "bidirectional"))
      (node (ref "RALT") (pin "MX2") (pinfunction "P1_MX2") (pintype "bidirectional"))
      (node (ref "SCOLON") (pin "MX2") (pinfunction "P1_MX2") (pintype "bidirectional"))
      (node (ref "TEENSY2.0") (pin "D0") (pinfunction "_D0_D0") (pintype "bidirectional"))
    )
    (net (code "11") (name "Net-(0-P0)") (class "Default")
      (node (ref "0") (pin "MX1") (pinfunction "P0_MX1") (pintype "bidirectional"))
      (node (ref "D110") (pin "A") (pinfunction "A_A") (pintype "passive"))
    )
    (net (code "12") (name "Net-(1-P0)") (class "Default")
      (node (ref "1") (pin "MX1") (pinfunction "P0_MX1") (pintype "bidirectional"))
      (node (ref "D101") (pin "A") (pinfunction "A_A") (pintype "passive"))
    )
    (net (code "13") (name "Net-(1-P1)") (class "Default")
      (node (ref "1") (pin "MX2") (pinfunction "P1_MX2") (pintype "bidirectional"))
      (node (ref "A") (pin "MX2") (pinfunction "P1_MX2") (pintype "bidirectional"))
      (node (ref "F1") (pin "MX2") (pinfunction "P1_MX2") (pintype "bidirectional"))
      (node (ref "Q") (pin "MX2") (pinfunction "P1_MX2") (pintype "bidirectional"))
      (node (ref "TEENSY2.0") (pin "F5") (pinfunction "_F5_F5") (pintype "bidirectional"))
      (node (ref "WIN") (pin "MX2") (pinfunction "P1_MX2") (pintype "bidirectional"))
      (node (ref "Z") (pin "MX2") (pinfunction "P1_MX2") (pintype "bidirectional"))
    )
    (net (code "14") (name "Net-(2-P0)") (class "Default")
      (node (ref "2") (pin "MX1") (pinfunction "P0_MX1") (pintype "bidirectional"))
      (node (ref "D102") (pin "A") (pinfunction "A_A") (pintype "passive"))
    )
    (net (code "15") (name "Net-(2-P1)") (class "Default")
      (node (ref "2") (pin "MX2") (pinfunction "P1_MX2") (pintype "bidirectional"))
      (node (ref "F2") (pin "MX2") (pinfunction "P1_MX2") (pintype "bidirectional"))
      (node (ref "LALT") (pin "MX2") (pinfunction "P1_MX2") (pintype "bidirectional"))
      (node (ref "S") (pin "MX2") (pinfunction "P1_MX2") (pintype "bidirectional"))
      (node (ref "TEENSY2.0") (pin "F4") (pinfunction "_F4_F4") (pintype "bidirectional"))
      (node (ref "W") (pin "MX2") (pinfunction "P1_MX2") (pintype "bidirectional"))
      (node (ref "X") (pin "MX2") (pinfunction "P1_MX2") (pintype "bidirectional"))
    )
    (net (code "16") (name "Net-(3-P0)") (class "Default")
      (node (ref "3") (pin "MX1") (pinfunction "P0_MX1") (pintype "bidirectional"))
      (node (ref "D103") (pin "A") (pinfunction "A_A") (pintype "passive"))
    )
    (net (code "17") (name "Net-(3-P1)") (class "Default")
      (node (ref "3") (pin "MX2") (pinfunction "P1_MX2") (pintype "bidirectional"))
      (node (ref "C") (pin "MX2") (pinfunction "P1_MX2") (pintype "bidirectional"))
      (node (ref "D") (pin "MX2") (pinfunction "P1_MX2") (pintype "bidirectional"))
      (node (ref "E") (pin "MX2") (pinfunction "P1_MX2") (pintype "bidirectional"))
      (node (ref "F3") (pin "MX2") (pinfunction "P1_MX2") (pintype "bidirectional"))
      (node (ref "TEENSY2.0") (pin "F1") (pinfunction "_F1_F1") (pintype "bidirectional"))
    )
    (net (code "18") (name "Net-(4-P0)") (class "Default")
      (node (ref "4") (pin "MX1") (pinfunction "P0_MX1") (pintype "bidirectional"))
      (node (ref "D104") (pin "A") (pinfunction "A_A") (pintype "passive"))
    )
    (net (code "19") (name "Net-(4-P1)") (class "Default")
      (node (ref "4") (pin "MX2") (pinfunction "P1_MX2") (pintype "bidirectional"))
      (node (ref "F") (pin "MX2") (pinfunction "P1_MX2") (pintype "bidirectional"))
      (node (ref "F4") (pin "MX2") (pinfunction "P1_MX2") (pintype "bidirectional"))
      (node (ref "R") (pin "MX2") (pinfunction "P1_MX2") (pintype "bidirectional"))
      (node (ref "TEENSY2.0") (pin "F0") (pinfunction "_F0_F0") (pintype "bidirectional"))
      (node (ref "V") (pin "MX2") (pinfunction "P1_MX2") (pintype "bidirectional"))
    )
    (net (code "20") (name "Net-(5-P0)") (class "Default")
      (node (ref "5") (pin "MX1") (pinfunction "P0_MX1") (pintype "bidirectional"))
      (node (ref "D105") (pin "A") (pinfunction "A_A") (pintype "passive"))
    )
    (net (code "21") (name "Net-(5-P1)") (class "Default")
      (node (ref "5") (pin "MX2") (pinfunction "P1_MX2") (pintype "bidirectional"))
      (node (ref "B") (pin "MX2") (pinfunction "P1_MX2") (pintype "bidirectional"))
      (node (ref "F5") (pin "MX2") (pinfunction "P1_MX2") (pintype "bidirectional"))
      (node (ref "G") (pin "MX2") (pinfunction "P1_MX2") (pintype "bidirectional"))
      (node (ref "T") (pin "MX2") (pinfunction "P1_MX2") (pintype "bidirectional"))
      (node (ref "TEENSY2.0") (pin "C7") (pinfunction "_C7_C7") (pintype "bidirectional"))
    )
    (net (code "22") (name "Net-(6-P0)") (class "Default")
      (node (ref "6") (pin "MX1") (pinfunction "P0_MX1") (pintype "bidirectional"))
      (node (ref "D106") (pin "A") (pinfunction "A_A") (pintype "passive"))
    )
    (net (code "23") (name "Net-(6-P1)") (class "Default")
      (node (ref "6") (pin "MX2") (pinfunction "P1_MX2") (pintype "bidirectional"))
      (node (ref "F6") (pin "MX2") (pinfunction "P1_MX2") (pintype "bidirectional"))
      (node (ref "H") (pin "MX2") (pinfunction "P1_MX2") (pintype "bidirectional"))
      (node (ref "N") (pin "MX2") (pinfunction "P1_MX2") (pintype "bidirectional"))
      (node (ref "SBAR") (pin "MX2") (pinfunction "P1_MX2") (pintype "bidirectional"))
      (node (ref "TEENSY2.0") (pin "C6") (pinfunction "_C6_C6") (pintype "bidirectional"))
      (node (ref "Y") (pin "MX2") (pinfunction "P1_MX2") (pintype "bidirectional"))
    )
    (net (code "24") (name "Net-(7-P0)") (class "Default")
      (node (ref "7") (pin "MX1") (pinfunction "P0_MX1") (pintype "bidirectional"))
      (node (ref "D107") (pin "A") (pinfunction "A_A") (pintype "passive"))
    )
    (net (code "25") (name "Net-(7-P1)") (class "Default")
      (node (ref "7") (pin "MX2") (pinfunction "P1_MX2") (pintype "bidirectional"))
      (node (ref "F7") (pin "MX2") (pinfunction "P1_MX2") (pintype "bidirectional"))
      (node (ref "J") (pin "MX2") (pinfunction "P1_MX2") (pintype "bidirectional"))
      (node (ref "M") (pin "MX2") (pinfunction "P1_MX2") (pintype "bidirectional"))
      (node (ref "TEENSY2.0") (pin "D3") (pinfunction "_D3_D3") (pintype "bidirectional"))
      (node (ref "U") (pin "MX2") (pinfunction "P1_MX2") (pintype "bidirectional"))
    )
    (net (code "26") (name "Net-(8-P0)") (class "Default")
      (node (ref "8") (pin "MX1") (pinfunction "P0_MX1") (pintype "bidirectional"))
      (node (ref "D108") (pin "A") (pinfunction "A_A") (pintype "passive"))
    )
    (net (code "27") (name "Net-(9-P0)") (class "Default")
      (node (ref "9") (pin "MX1") (pinfunction "P0_MX1") (pintype "bidirectional"))
      (node (ref "D109") (pin "A") (pinfunction "A_A") (pintype "passive"))
    )
    (net (code "28") (name "Net-(=-P0)") (class "Default")
      (node (ref "=") (pin "MX1") (pinfunction "P0_MX1") (pintype "bidirectional"))
      (node (ref "D112") (pin "A") (pinfunction "A_A") (pintype "passive"))
    )
    (net (code "29") (name "Net-(=-P1)") (class "Default")
      (node (ref "=") (pin "MX2") (pinfunction "P1_MX2") (pintype "bidirectional"))
      (node (ref "F12") (pin "MX2") (pinfunction "P1_MX2") (pintype "bidirectional"))
      (node (ref "RCTRL") (pin "MX2") (pinfunction "P1_MX2") (pintype "bidirectional"))
      (node (ref "TEENSY2.0") (pin "B3") (pinfunction "_B3_B3") (pintype "bidirectional"))
      (node (ref "]") (pin "MX2") (pinfunction "P1_MX2") (pintype "bidirectional"))
    )
    (net (code "30") (name "Net-(A-P0)") (class "Default")
      (node (ref "A") (pin "MX1") (pinfunction "P0_MX1") (pintype "bidirectional"))
      (node (ref "D301") (pin "A") (pinfunction "A_A") (pintype "passive"))
    )
    (net (code "31") (name "Net-(B-P0)") (class "Default")
      (node (ref "B") (pin "MX1") (pinfunction "P0_MX1") (pintype "bidirectional"))
      (node (ref "D405") (pin "A") (pinfunction "A_A") (pintype "passive"))
    )
    (net (code "32") (name "Net-(BKSPACE-P0)") (class "Default")
      (node (ref "BKSPACE") (pin "MX1") (pinfunction "P0_MX1") (pintype "bidirectional"))
      (node (ref "D114") (pin "A") (pinfunction "A_A") (pintype "passive"))
    )
    (net (code "33") (name "Net-(BKSPACE-P1)") (class "Default")
      (node (ref "BKSPACE") (pin "MX2") (pinfunction "P1_MX2") (pintype "bidirectional"))
      (node (ref "DARROW") (pin "MX2") (pinfunction "P1_MX2") (pintype "bidirectional"))
      (node (ref "PAUSE") (pin "MX2") (pinfunction "P1_MX2") (pintype "bidirectional"))
      (node (ref "TEENSY2.0") (pin "B1") (pinfunction "_B1_B1") (pintype "bidirectional"))
      (node (ref "UARROW") (pin "MX2") (pinfunction "P1_MX2") (pintype "bidirectional"))
    )
    (net (code "34") (name "Net-(C-P0)") (class "Default")
      (node (ref "C") (pin "MX1") (pinfunction "P0_MX1") (pintype "bidirectional"))
      (node (ref "D403") (pin "A") (pinfunction "A_A") (pintype "passive"))
    )
    (net (code "35") (name "Net-(CAPSLK-P0)") (class "Default")
      (node (ref "CAPSLK") (pin "MX1") (pinfunction "P0_MX1") (pintype "bidirectional"))
      (node (ref "D300") (pin "A") (pinfunction "A_A") (pintype "passive"))
    )
    (net (code "36") (name "Net-(CAPSLK-P1)") (class "Default")
      (node (ref "CAPSLK") (pin "MX2") (pinfunction "P1_MX2") (pintype "bidirectional"))
      (node (ref "ESC") (pin "MX2") (pinfunction "P1_MX2") (pintype "bidirectional"))
      (node (ref "LCTRL") (pin "MX2") (pinfunction "P1_MX2") (pintype "bidirectional"))
      (node (ref "LSHIFT") (pin "MX2") (pinfunction "P1_MX2") (pintype "bidirectional"))
      (node (ref "TAB") (pin "MX2") (pinfunction "P1_MX2") (pintype "bidirectional"))
      (node (ref "TEENSY2.0") (pin "F6") (pinfunction "_F6_F6") (pintype "bidirectional"))
      (node (ref "`") (pin "MX2") (pinfunction "P1_MX2") (pintype "bidirectional"))
    )
    (net (code "37") (name "Net-(CAPSLK-PadLED+)") (class "Default")
      (node (ref "CAPSLK") (pin "LED+") (pinfunction "LED+_LED+") (pintype "bidirectional"))
      (node (ref "HEADER") (pin "1") (pinfunction "1_1") (pintype "passive"))
      (node (ref "R1") (pin "1") (pinfunction "1_1") (pintype "passive"))
    )
    (net (code "38") (name "Net-(D-P0)") (class "Default")
      (node (ref "D") (pin "MX1") (pinfunction "P0_MX1") (pintype "bidirectional"))
      (node (ref "D303") (pin "A") (pinfunction "A_A") (pintype "passive"))
    )
    (net (code "39") (name "Net-(DARROW-P0)") (class "Default")
      (node (ref "D514") (pin "A") (pinfunction "A_A") (pintype "passive"))
      (node (ref "DARROW") (pin "MX1") (pinfunction "P0_MX1") (pintype "bidirectional"))
    )
    (net (code "40") (name "Net-(DELETE-P0)") (class "Default")
      (node (ref "D015") (pin "A") (pinfunction "A_A") (pintype "passive"))
      (node (ref "DELETE") (pin "MX1") (pinfunction "P0_MX1") (pintype "bidirectional"))
    )
    (net (code "41") (name "Net-(DELETE-P1)") (class "Default")
      (node (ref "DELETE") (pin "MX2") (pinfunction "P1_MX2") (pintype "bidirectional"))
      (node (ref "END") (pin "MX2") (pinfunction "P1_MX2") (pintype "bidirectional"))
      (node (ref "HOME") (pin "MX2") (pinfunction "P1_MX2") (pintype "bidirectional"))
      (node (ref "PGDOWN") (pin "MX2") (pinfunction "P1_MX2") (pintype "bidirectional"))
      (node (ref "PGUP") (pin "MX2") (pinfunction "P1_MX2") (pintype "bidirectional"))
      (node (ref "RARROW") (pin "MX2") (pinfunction "P1_MX2") (pintype "bidirectional"))
      (node (ref "TEENSY2.0") (pin "B0") (pinfunction "_B0_B0") (pintype "bidirectional"))
    )
    (net (code "42") (name "Net-(E-P0)") (class "Default")
      (node (ref "D203") (pin "A") (pinfunction "A_A") (pintype "passive"))
      (node (ref "E") (pin "MX1") (pinfunction "P0_MX1") (pintype "bidirectional"))
    )
    (net (code "43") (name "Net-(END-P0)") (class "Default")
      (node (ref "D415") (pin "A") (pinfunction "A_A") (pintype "passive"))
      (node (ref "END") (pin "MX1") (pinfunction "P0_MX1") (pintype "bidirectional"))
    )
    (net (code "44") (name "Net-(ENTER-P0)") (class "Default")
      (node (ref "D313") (pin "A") (pinfunction "A_A") (pintype "passive"))
      (node (ref "ENTER") (pin "MX1") (pinfunction "P0_MX1") (pintype "bidirectional"))
    )
    (net (code "45") (name "Net-(ENTER-P1)") (class "Default")
      (node (ref "ENTER") (pin "MX2") (pinfunction "P1_MX2") (pintype "bidirectional"))
      (node (ref "LARROW") (pin "MX2") (pinfunction "P1_MX2") (pintype "bidirectional"))
      (node (ref "PRTSC") (pin "MX2") (pinfunction "P1_MX2") (pintype "bidirectional"))
      (node (ref "RSHIFT") (pin "MX2") (pinfunction "P1_MX2") (pintype "bidirectional"))
      (node (ref "TEENSY2.0") (pin "B2") (pinfunction "_B2_B2") (pintype "bidirectional"))
      (node (ref "\\\\") (pin "MX2") (pinfunction "P1_MX2") (pintype "bidirectional"))
    )
    (net (code "46") (name "Net-(ESC-P0)") (class "Default")
      (node (ref "D000") (pin "A") (pinfunction "A_A") (pintype "passive"))
      (node (ref "ESC") (pin "MX1") (pinfunction "P0_MX1") (pintype "bidirectional"))
    )
    (net (code "47") (name "Net-(F-P0)") (class "Default")
      (node (ref "D304") (pin "A") (pinfunction "A_A") (pintype "passive"))
      (node (ref "F") (pin "MX1") (pinfunction "P0_MX1") (pintype "bidirectional"))
    )
    (net (code "48") (name "Net-(F1-P0)") (class "Default")
      (node (ref "D001") (pin "A") (pinfunction "A_A") (pintype "passive"))
      (node (ref "F1") (pin "MX1") (pinfunction "P0_MX1") (pintype "bidirectional"))
    )
    (net (code "49") (name "Net-(F2-P0)") (class "Default")
      (node (ref "D002") (pin "A") (pinfunction "A_A") (pintype "passive"))
      (node (ref "F2") (pin "MX1") (pinfunction "P0_MX1") (pintype "bidirectional"))
    )
    (net (code "50") (name "Net-(F3-P0)") (class "Default")
      (node (ref "D003") (pin "A") (pinfunction "A_A") (pintype "passive"))
      (node (ref "F3") (pin "MX1") (pinfunction "P0_MX1") (pintype "bidirectional"))
    )
    (net (code "51") (name "Net-(F4-P0)") (class "Default")
      (node (ref "D004") (pin "A") (pinfunction "A_A") (pintype "passive"))
      (node (ref "F4") (pin "MX1") (pinfunction "P0_MX1") (pintype "bidirectional"))
    )
    (net (code "52") (name "Net-(F5-P0)") (class "Default")
      (node (ref "D005") (pin "A") (pinfunction "A_A") (pintype "passive"))
      (node (ref "F5") (pin "MX1") (pinfunction "P0_MX1") (pintype "bidirectional"))
    )
    (net (code "53") (name "Net-(F6-P0)") (class "Default")
      (node (ref "D006") (pin "A") (pinfunction "A_A") (pintype "passive"))
      (node (ref "F6") (pin "MX1") (pinfunction "P0_MX1") (pintype "bidirectional"))
    )
    (net (code "54") (name "Net-(F7-P0)") (class "Default")
      (node (ref "D007") (pin "A") (pinfunction "A_A") (pintype "passive"))
      (node (ref "F7") (pin "MX1") (pinfunction "P0_MX1") (pintype "bidirectional"))
    )
    (net (code "55") (name "Net-(F8-P0)") (class "Default")
      (node (ref "D008") (pin "A") (pinfunction "A_A") (pintype "passive"))
      (node (ref "F8") (pin "MX1") (pinfunction "P0_MX1") (pintype "bidirectional"))
    )
    (net (code "56") (name "Net-(F9-P0)") (class "Default")
      (node (ref "D009") (pin "A") (pinfunction "A_A") (pintype "passive"))
      (node (ref "F9") (pin "MX1") (pinfunction "P0_MX1") (pintype "bidirectional"))
    )
    (net (code "57") (name "Net-(F10-P0)") (class "Default")
      (node (ref "D010") (pin "A") (pinfunction "A_A") (pintype "passive"))
      (node (ref "F10") (pin "MX1") (pinfunction "P0_MX1") (pintype "bidirectional"))
    )
    (net (code "58") (name "Net-(F11-P0)") (class "Default")
      (node (ref "D011") (pin "A") (pinfunction "A_A") (pintype "passive"))
      (node (ref "F11") (pin "MX1") (pinfunction "P0_MX1") (pintype "bidirectional"))
    )
    (net (code "59") (name "Net-(F12-P0)") (class "Default")
      (node (ref "D012") (pin "A") (pinfunction "A_A") (pintype "passive"))
      (node (ref "F12") (pin "MX1") (pinfunction "P0_MX1") (pintype "bidirectional"))
    )
    (net (code "60") (name "Net-(FN-P0)") (class "Default")
      (node (ref "D511") (pin "A") (pinfunction "A_A") (pintype "passive"))
      (node (ref "FN") (pin "MX1") (pinfunction "P0_MX1") (pintype "bidirectional"))
    )
    (net (code "61") (name "Net-(G-P0)") (class "Default")
      (node (ref "D305") (pin "A") (pinfunction "A_A") (pintype "passive"))
      (node (ref "G") (pin "MX1") (pinfunction "P0_MX1") (pintype "bidirectional"))
    )
    (net (code "62") (name "Net-(H-P0)") (class "Default")
      (node (ref "D306") (pin "A") (pinfunction "A_A") (pintype "passive"))
      (node (ref "H") (pin "MX1") (pinfunction "P0_MX1") (pintype "bidirectional"))
    )
    (net (code "63") (name "Net-(HOME-P0)") (class "Default")
      (node (ref "D115") (pin "A") (pinfunction "A_A") (pintype "passive"))
      (node (ref "HOME") (pin "MX1") (pinfunction "P0_MX1") (pintype "bidirectional"))
    )
    (net (code "64") (name "Net-(I-P0)") (class "Default")
      (node (ref "D208") (pin "A") (pinfunction "A_A") (pintype "passive"))
      (node (ref "I") (pin "MX1") (pinfunction "P0_MX1") (pintype "bidirectional"))
    )
    (net (code "65") (name "Net-(J-P0)") (class "Default")
      (node (ref "D307") (pin "A") (pinfunction "A_A") (pintype "passive"))
      (node (ref "J") (pin "MX1") (pinfunction "P0_MX1") (pintype "bidirectional"))
    )
    (net (code "66") (name "Net-(K-P0)") (class "Default")
      (node (ref "D308") (pin "A") (pinfunction "A_A") (pintype "passive"))
      (node (ref "K") (pin "MX1") (pinfunction "P0_MX1") (pintype "bidirectional"))
    )
    (net (code "67") (name "Net-(L-P0)") (class "Default")
      (node (ref "D309") (pin "A") (pinfunction "A_A") (pintype "passive"))
      (node (ref "L") (pin "MX1") (pinfunction "P0_MX1") (pintype "bidirectional"))
    )
    (net (code "68") (name "Net-(LALT-P0)") (class "Default")
      (node (ref "D502") (pin "A") (pinfunction "A_A") (pintype "passive"))
      (node (ref "LALT") (pin "MX1") (pinfunction "P0_MX1") (pintype "bidirectional"))
    )
    (net (code "69") (name "Net-(LARROW-P0)") (class "Default")
      (node (ref "D513") (pin "A") (pinfunction "A_A") (pintype "passive"))
      (node (ref "LARROW") (pin "MX1") (pinfunction "P0_MX1") (pintype "bidirectional"))
    )
    (net (code "70") (name "Net-(LCTRL-P0)") (class "Default")
      (node (ref "D500") (pin "A") (pinfunction "A_A") (pintype "passive"))
      (node (ref "LCTRL") (pin "MX1") (pinfunction "P0_MX1") (pintype "bidirectional"))
    )
    (net (code "71") (name "Net-(LSHIFT-P0)") (class "Default")
      (node (ref "D400") (pin "A") (pinfunction "A_A") (pintype "passive"))
      (node (ref "LSHIFT") (pin "MX1") (pinfunction "P0_MX1") (pintype "bidirectional"))
    )
    (net (code "72") (name "Net-(M-P0)") (class "Default")
      (node (ref "D407") (pin "A") (pinfunction "A_A") (pintype "passive"))
      (node (ref "M") (pin "MX1") (pinfunction "P0_MX1") (pintype "bidirectional"))
    )
    (net (code "73") (name "Net-(N-P0)") (class "Default")
      (node (ref "D406") (pin "A") (pinfunction "A_A") (pintype "passive"))
      (node (ref "N") (pin "MX1") (pinfunction "P0_MX1") (pintype "bidirectional"))
    )
    (net (code "74") (name "Net-(O-P0)") (class "Default")
      (node (ref "D209") (pin "A") (pinfunction "A_A") (pintype "passive"))
      (node (ref "O") (pin "MX1") (pinfunction "P0_MX1") (pintype "bidirectional"))
    )
    (net (code "75") (name "Net-(P-P0)") (class "Default")
      (node (ref "D210") (pin "A") (pinfunction "A_A") (pintype "passive"))
      (node (ref "P") (pin "MX1") (pinfunction "P0_MX1") (pintype "bidirectional"))
    )
    (net (code "76") (name "Net-(PAUSE-P0)") (class "Default")
      (node (ref "D014") (pin "A") (pinfunction "A_A") (pintype "passive"))
      (node (ref "PAUSE") (pin "MX1") (pinfunction "P0_MX1") (pintype "bidirectional"))
    )
    (net (code "77") (name "Net-(PGDOWN-P0)") (class "Default")
      (node (ref "D315") (pin "A") (pinfunction "A_A") (pintype "passive"))
      (node (ref "PGDOWN") (pin "MX1") (pinfunction "P0_MX1") (pintype "bidirectional"))
    )
    (net (code "78") (name "Net-(PGUP-P0)") (class "Default")
      (node (ref "D215") (pin "A") (pinfunction "A_A") (pintype "passive"))
      (node (ref "PGUP") (pin "MX1") (pinfunction "P0_MX1") (pintype "bidirectional"))
    )
    (net (code "79") (name "Net-(PRTSC-P0)") (class "Default")
      (node (ref "D013") (pin "A") (pinfunction "A_A") (pintype "passive"))
      (node (ref "PRTSC") (pin "MX1") (pinfunction "P0_MX1") (pintype "bidirectional"))
    )
    (net (code "80") (name "Net-(Q-P0)") (class "Default")
      (node (ref "D201") (pin "A") (pinfunction "A_A") (pintype "passive"))
      (node (ref "Q") (pin "MX1") (pinfunction "P0_MX1") (pintype "bidirectional"))
    )
    (net (code "81") (name "Net-(R-P0)") (class "Default")
      (node (ref "D204") (pin "A") (pinfunction "A_A") (pintype "passive"))
      (node (ref "R") (pin "MX1") (pinfunction "P0_MX1") (pintype "bidirectional"))
    )
    (net (code "82") (name "Net-(RALT-P0)") (class "Default")
      (node (ref "D510") (pin "A") (pinfunction "A_A") (pintype "passive"))
      (node (ref "RALT") (pin "MX1") (pinfunction "P0_MX1") (pintype "bidirectional"))
    )
    (net (code "83") (name "Net-(RARROW-P0)") (class "Default")
      (node (ref "D515") (pin "A") (pinfunction "A_A") (pintype "passive"))
      (node (ref "RARROW") (pin "MX1") (pinfunction "P0_MX1") (pintype "bidirectional"))
    )
    (net (code "84") (name "Net-(RCTRL-P0)") (class "Default")
      (node (ref "D512") (pin "A") (pinfunction "A_A") (pintype "passive"))
      (node (ref "RCTRL") (pin "MX1") (pinfunction "P0_MX1") (pintype "bidirectional"))
    )
    (net (code "85") (name "Net-(RSHIFT-P0)") (class "Default")
      (node (ref "D413") (pin "A") (pinfunction "A_A") (pintype "passive"))
      (node (ref "RSHIFT") (pin "MX1") (pinfunction "P0_MX1") (pintype "bidirectional"))
    )
    (net (code "86") (name "Net-(S-P0)") (class "Default")
      (node (ref "D302") (pin "A") (pinfunction "A_A") (pintype "passive"))
      (node (ref "S") (pin "MX1") (pinfunction "P0_MX1") (pintype "bidirectional"))
    )
    (net (code "87") (name "Net-(SBAR-P0)") (class "Default")
      (node (ref "D506") (pin "A") (pinfunction "A_A") (pintype "passive"))
      (node (ref "SBAR") (pin "MX1") (pinfunction "P0_MX1") (pintype "bidirectional"))
    )
    (net (code "88") (name "Net-(SCOLON-P0)") (class "Default")
      (node (ref "D310") (pin "A") (pinfunction "A_A") (pintype "passive"))
      (node (ref "SCOLON") (pin "MX1") (pinfunction "P0_MX1") (pintype "bidirectional"))
    )
    (net (code "89") (name "Net-(T-P0)") (class "Default")
      (node (ref "D205") (pin "A") (pinfunction "A_A") (pintype "passive"))
      (node (ref "T") (pin "MX1") (pinfunction "P0_MX1") (pintype "bidirectional"))
    )
    (net (code "90") (name "Net-(TAB-P0)") (class "Default")
      (node (ref "D200") (pin "A") (pinfunction "A_A") (pintype "passive"))
      (node (ref "TAB") (pin "MX1") (pinfunction "P0_MX1") (pintype "bidirectional"))
    )
    (net (code "91") (name "Net-(TEENSY2.0-_5V2)") (class "Default")
      (node (ref "HEADER") (pin "3") (pinfunction "3_3") (pintype "passive"))
      (node (ref "R1") (pin "2") (pinfunction "2_2") (pintype "passive"))
      (node (ref "TEENSY2.0") (pin "5V2") (pinfunction "_5V2_5V2") (pintype "bidirectional"))
    )
    (net (code "92") (name "Net-(TEENSY2.0-_B4)") (class "Default")
      (node (ref "D100") (pin "C") (pinfunction "C_C") (pintype "passive"))
      (node (ref "D101") (pin "C") (pinfunction "C_C") (pintype "passive"))
      (node (ref "D102") (pin "C") (pinfunction "C_C") (pintype "passive"))
      (node (ref "D103") (pin "C") (pinfunction "C_C") (pintype "passive"))
      (node (ref "D104") (pin "C") (pinfunction "C_C") (pintype "passive"))
      (node (ref "D105") (pin "C") (pinfunction "C_C") (pintype "passive"))
      (node (ref "D106") (pin "C") (pinfunction "C_C") (pintype "passive"))
      (node (ref "D107") (pin "C") (pinfunction "C_C") (pintype "passive"))
      (node (ref "D108") (pin "C") (pinfunction "C_C") (pintype "passive"))
      (node (ref "D109") (pin "C") (pinfunction "C_C") (pintype "passive"))
      (node (ref "D110") (pin "C") (pinfunction "C_C") (pintype "passive"))
      (node (ref "D111") (pin "C") (pinfunction "C_C") (pintype "passive"))
      (node (ref "D112") (pin "C") (pinfunction "C_C") (pintype "passive"))
      (node (ref "D114") (pin "C") (pinfunction "C_C") (pintype "passive"))
      (node (ref "D115") (pin "C") (pinfunction "C_C") (pintype "passive"))
      (node (ref "TEENSY2.0") (pin "B4") (pinfunction "_B4_B4") (pintype "bidirectional"))
    )
    (net (code "93") (name "Net-(TEENSY2.0-_B5)") (class "Default")
      (node (ref "D200") (pin "C") (pinfunction "C_C") (pintype "passive"))
      (node (ref "D201") (pin "C") (pinfunction "C_C") (pintype "passive"))
      (node (ref "D202") (pin "C") (pinfunction "C_C") (pintype "passive"))
      (node (ref "D203") (pin "C") (pinfunction "C_C") (pintype "passive"))
      (node (ref "D204") (pin "C") (pinfunction "C_C") (pintype "passive"))
      (node (ref "D205") (pin "C") (pinfunction "C_C") (pintype "passive"))
      (node (ref "D206") (pin "C") (pinfunction "C_C") (pintype "passive"))
      (node (ref "D207") (pin "C") (pinfunction "C_C") (pintype "passive"))
      (node (ref "D208") (pin "C") (pinfunction "C_C") (pintype "passive"))
      (node (ref "D209") (pin "C") (pinfunction "C_C") (pintype "passive"))
      (node (ref "D210") (pin "C") (pinfunction "C_C") (pintype "passive"))
      (node (ref "D211") (pin "C") (pinfunction "C_C") (pintype "passive"))
      (node (ref "D212") (pin "C") (pinfunction "C_C") (pintype "passive"))
      (node (ref "D213") (pin "C") (pinfunction "C_C") (pintype "passive"))
      (node (ref "D215") (pin "C") (pinfunction "C_C") (pintype "passive"))
      (node (ref "TEENSY2.0") (pin "B5") (pinfunction "_B5_B5") (pintype "bidirectional"))
    )
    (net (code "94") (name "Net-(TEENSY2.0-_B6)") (class "Default")
      (node (ref "D300") (pin "C") (pinfunction "C_C") (pintype "passive"))
      (node (ref "D301") (pin "C") (pinfunction "C_C") (pintype "passive"))
      (node (ref "D302") (pin "C") (pinfunction "C_C") (pintype "passive"))
      (node (ref "D303") (pin "C") (pinfunction "C_C") (pintype "passive"))
      (node (ref "D304") (pin "C") (pinfunction "C_C") (pintype "passive"))
      (node (ref "D305") (pin "C") (pinfunction "C_C") (pintype "passive"))
      (node (ref "D306") (pin "C") (pinfunction "C_C") (pintype "passive"))
      (node (ref "D307") (pin "C") (pinfunction "C_C") (pintype "passive"))
      (node (ref "D308") (pin "C") (pinfunction "C_C") (pintype "passive"))
      (node (ref "D309") (pin "C") (pinfunction "C_C") (pintype "passive"))
      (node (ref "D310") (pin "C") (pinfunction "C_C") (pintype "passive"))
      (node (ref "D311") (pin "C") (pinfunction "C_C") (pintype "passive"))
      (node (ref "D313") (pin "C") (pinfunction "C_C") (pintype "passive"))
      (node (ref "D315") (pin "C") (pinfunction "C_C") (pintype "passive"))
      (node (ref "TEENSY2.0") (pin "B6") (pinfunction "_B6_B6") (pintype "bidirectional"))
    )
    (net (code "95") (name "Net-(TEENSY2.0-_D4)") (class "Default")
      (node (ref "CAPSLK") (pin "LED-") (pinfunction "LED-_LED-") (pintype "bidirectional"))
      (node (ref "HEADER") (pin "2") (pinfunction "2_2") (pintype "passive"))
      (node (ref "TEENSY2.0") (pin "D4") (pinfunction "_D4_D4") (pintype "bidirectional"))
    )
    (net (code "96") (name "Net-(TEENSY2.0-_D5)") (class "Default")
      (node (ref "D500") (pin "C") (pinfunction "C_C") (pintype "passive"))
      (node (ref "D501") (pin "C") (pinfunction "C_C") (pintype "passive"))
      (node (ref "D502") (pin "C") (pinfunction "C_C") (pintype "passive"))
      (node (ref "D506") (pin "C") (pinfunction "C_C") (pintype "passive"))
      (node (ref "D510") (pin "C") (pinfunction "C_C") (pintype "passive"))
      (node (ref "D511") (pin "C") (pinfunction "C_C") (pintype "passive"))
      (node (ref "D512") (pin "C") (pinfunction "C_C") (pintype "passive"))
      (node (ref "D513") (pin "C") (pinfunction "C_C") (pintype "passive"))
      (node (ref "D514") (pin "C") (pinfunction "C_C") (pintype "passive"))
      (node (ref "D515") (pin "C") (pinfunction "C_C") (pintype "passive"))
      (node (ref "TEENSY2.0") (pin "D5") (pinfunction "_D5_D5") (pintype "bidirectional"))
    )
    (net (code "97") (name "Net-(TEENSY2.0-_D6)") (class "Default")
      (node (ref "HEADER") (pin "6") (pinfunction "6_6") (pintype "passive"))
      (node (ref "TEENSY2.0") (pin "D6") (pinfunction "_D6_D6") (pintype "bidirectional"))
    )
    (net (code "98") (name "Net-(TEENSY2.0-_D7)") (class "Default")
      (node (ref "D000") (pin "C") (pinfunction "C_C") (pintype "passive"))
      (node (ref "D001") (pin "C") (pinfunction "C_C") (pintype "passive"))
      (node (ref "D002") (pin "C") (pinfunction "C_C") (pintype "passive"))
      (node (ref "D003") (pin "C") (pinfunction "C_C") (pintype "passive"))
      (node (ref "D004") (pin "C") (pinfunction "C_C") (pintype "passive"))
      (node (ref "D005") (pin "C") (pinfunction "C_C") (pintype "passive"))
      (node (ref "D006") (pin "C") (pinfunction "C_C") (pintype "passive"))
      (node (ref "D007") (pin "C") (pinfunction "C_C") (pintype "passive"))
      (node (ref "D008") (pin "C") (pinfunction "C_C") (pintype "passive"))
      (node (ref "D009") (pin "C") (pinfunction "C_C") (pintype "passive"))
      (node (ref "D010") (pin "C") (pinfunction "C_C") (pintype "passive"))
      (node (ref "D011") (pin "C") (pinfunction "C_C") (pintype "passive"))
      (node (ref "D012") (pin "C") (pinfunction "C_C") (pintype "passive"))
      (node (ref "D013") (pin "C") (pinfunction "C_C") (pintype "passive"))
      (node (ref "D014") (pin "C") (pinfunction "C_C") (pintype "passive"))
      (node (ref "D015") (pin "C") (pinfunction "C_C") (pintype "passive"))
      (node (ref "TEENSY2.0") (pin "D7") (pinfunction "_D7_D7") (pintype "bidirectional"))
    )
    (net (code "99") (name "Net-(TEENSY2.0-_E6)") (class "Default")
      (node (ref "HEADER") (pin "5") (pinfunction "5_5") (pintype "passive"))
      (node (ref "TEENSY2.0") (pin "E6") (pinfunction "_E6_E6") (pintype "bidirectional"))
    )
    (net (code "100") (name "Net-(TEENSY2.0-_F7)") (class "Default")
      (node (ref "D400") (pin "C") (pinfunction "C_C") (pintype "passive"))
      (node (ref "D401") (pin "C") (pinfunction "C_C") (pintype "passive"))
      (node (ref "D402") (pin "C") (pinfunction "C_C") (pintype "passive"))
      (node (ref "D403") (pin "C") (pinfunction "C_C") (pintype "passive"))
      (node (ref "D404") (pin "C") (pinfunction "C_C") (pintype "passive"))
      (node (ref "D405") (pin "C") (pinfunction "C_C") (pintype "passive"))
      (node (ref "D406") (pin "C") (pinfunction "C_C") (pintype "passive"))
      (node (ref "D407") (pin "C") (pinfunction "C_C") (pintype "passive"))
      (node (ref "D408") (pin "C") (pinfunction "C_C") (pintype "passive"))
      (node (ref "D409") (pin "C") (pinfunction "C_C") (pintype "passive"))
      (node (ref "D410") (pin "C") (pinfunction "C_C") (pintype "passive"))
      (node (ref "D413") (pin "C") (pinfunction "C_C") (pintype "passive"))
      (node (ref "D414") (pin "C") (pinfunction "C_C") (pintype "passive"))
      (node (ref "D415") (pin "C") (pinfunction "C_C") (pintype "passive"))
      (node (ref "TEENSY2.0") (pin "F7") (pinfunction "_F7_F7") (pintype "bidirectional"))
    )
    (net (code "101") (name "Net-(U-P0)") (class "Default")
      (node (ref "D207") (pin "A") (pinfunction "A_A") (pintype "passive"))
      (node (ref "U") (pin "MX1") (pinfunction "P0_MX1") (pintype "bidirectional"))
    )
    (net (code "102") (name "Net-(UARROW-P0)") (class "Default")
      (node (ref "D414") (pin "A") (pinfunction "A_A") (pintype "passive"))
      (node (ref "UARROW") (pin "MX1") (pinfunction "P0_MX1") (pintype "bidirectional"))
    )
    (net (code "103") (name "Net-(V-P0)") (class "Default")
      (node (ref "D404") (pin "A") (pinfunction "A_A") (pintype "passive"))
      (node (ref "V") (pin "MX1") (pinfunction "P0_MX1") (pintype "bidirectional"))
    )
    (net (code "104") (name "Net-(W-P0)") (class "Default")
      (node (ref "D202") (pin "A") (pinfunction "A_A") (pintype "passive"))
      (node (ref "W") (pin "MX1") (pinfunction "P0_MX1") (pintype "bidirectional"))
    )
    (net (code "105") (name "Net-(WIN-P0)") (class "Default")
      (node (ref "D501") (pin "A") (pinfunction "A_A") (pintype "passive"))
      (node (ref "WIN") (pin "MX1") (pinfunction "P0_MX1") (pintype "bidirectional"))
    )
    (net (code "106") (name "Net-(X-P0)") (class "Default")
      (node (ref "D402") (pin "A") (pinfunction "A_A") (pintype "passive"))
      (node (ref "X") (pin "MX1") (pinfunction "P0_MX1") (pintype "bidirectional"))
    )
    (net (code "107") (name "Net-(Y-P0)") (class "Default")
      (node (ref "D206") (pin "A") (pinfunction "A_A") (pintype "passive"))
      (node (ref "Y") (pin "MX1") (pinfunction "P0_MX1") (pintype "bidirectional"))
    )
    (net (code "108") (name "Net-(Z-P0)") (class "Default")
      (node (ref "D401") (pin "A") (pinfunction "A_A") (pintype "passive"))
      (node (ref "Z") (pin "MX1") (pinfunction "P0_MX1") (pintype "bidirectional"))
    )
    (net (code "109") (name "Net-([-P0)") (class "Default")
      (node (ref "D211") (pin "A") (pinfunction "A_A") (pintype "passive"))
      (node (ref "[") (pin "MX1") (pinfunction "P0_MX1") (pintype "bidirectional"))
    )
    (net (code "110") (name "Net-(\\\\-P0)") (class "Default")
      (node (ref "D213") (pin "A") (pinfunction "A_A") (pintype "passive"))
      (node (ref "\\\\") (pin "MX1") (pinfunction "P0_MX1") (pintype "bidirectional"))
    )
    (net (code "111") (name "Net-(]-P0)") (class "Default")
      (node (ref "D212") (pin "A") (pinfunction "A_A") (pintype "passive"))
      (node (ref "]") (pin "MX1") (pinfunction "P0_MX1") (pintype "bidirectional"))
    )
    (net (code "112") (name "Net-(`-P0)") (class "Default")
      (node (ref "D100") (pin "A") (pinfunction "A_A") (pintype "passive"))
      (node (ref "`") (pin "MX1") (pinfunction "P0_MX1") (pintype "bidirectional"))
    )
    (net (code "113") (name "unconnected-(TEENSY2.0-5V-Pad+5V)") (class "Default")
      (node (ref "TEENSY2.0") (pin "+5V") (pinfunction "5V_+5V") (pintype "bidirectional"))
    )
    (net (code "114") (name "unconnected-(TEENSY2.0-_REF-PadREF)") (class "Default")
      (node (ref "TEENSY2.0") (pin "REF") (pinfunction "_REF_REF") (pintype "bidirectional"))
    )
    (net (code "115") (name "unconnected-(TEENSY2.0-_RST-PadRST)") (class "Default")
      (node (ref "TEENSY2.0") (pin "RST") (pinfunction "_RST_RST") (pintype "bidirectional"))
    )
  )
)
